# ASCII_10_FPGA_misc.net
KiCad netlist of a schematic drawn in Altium Designer
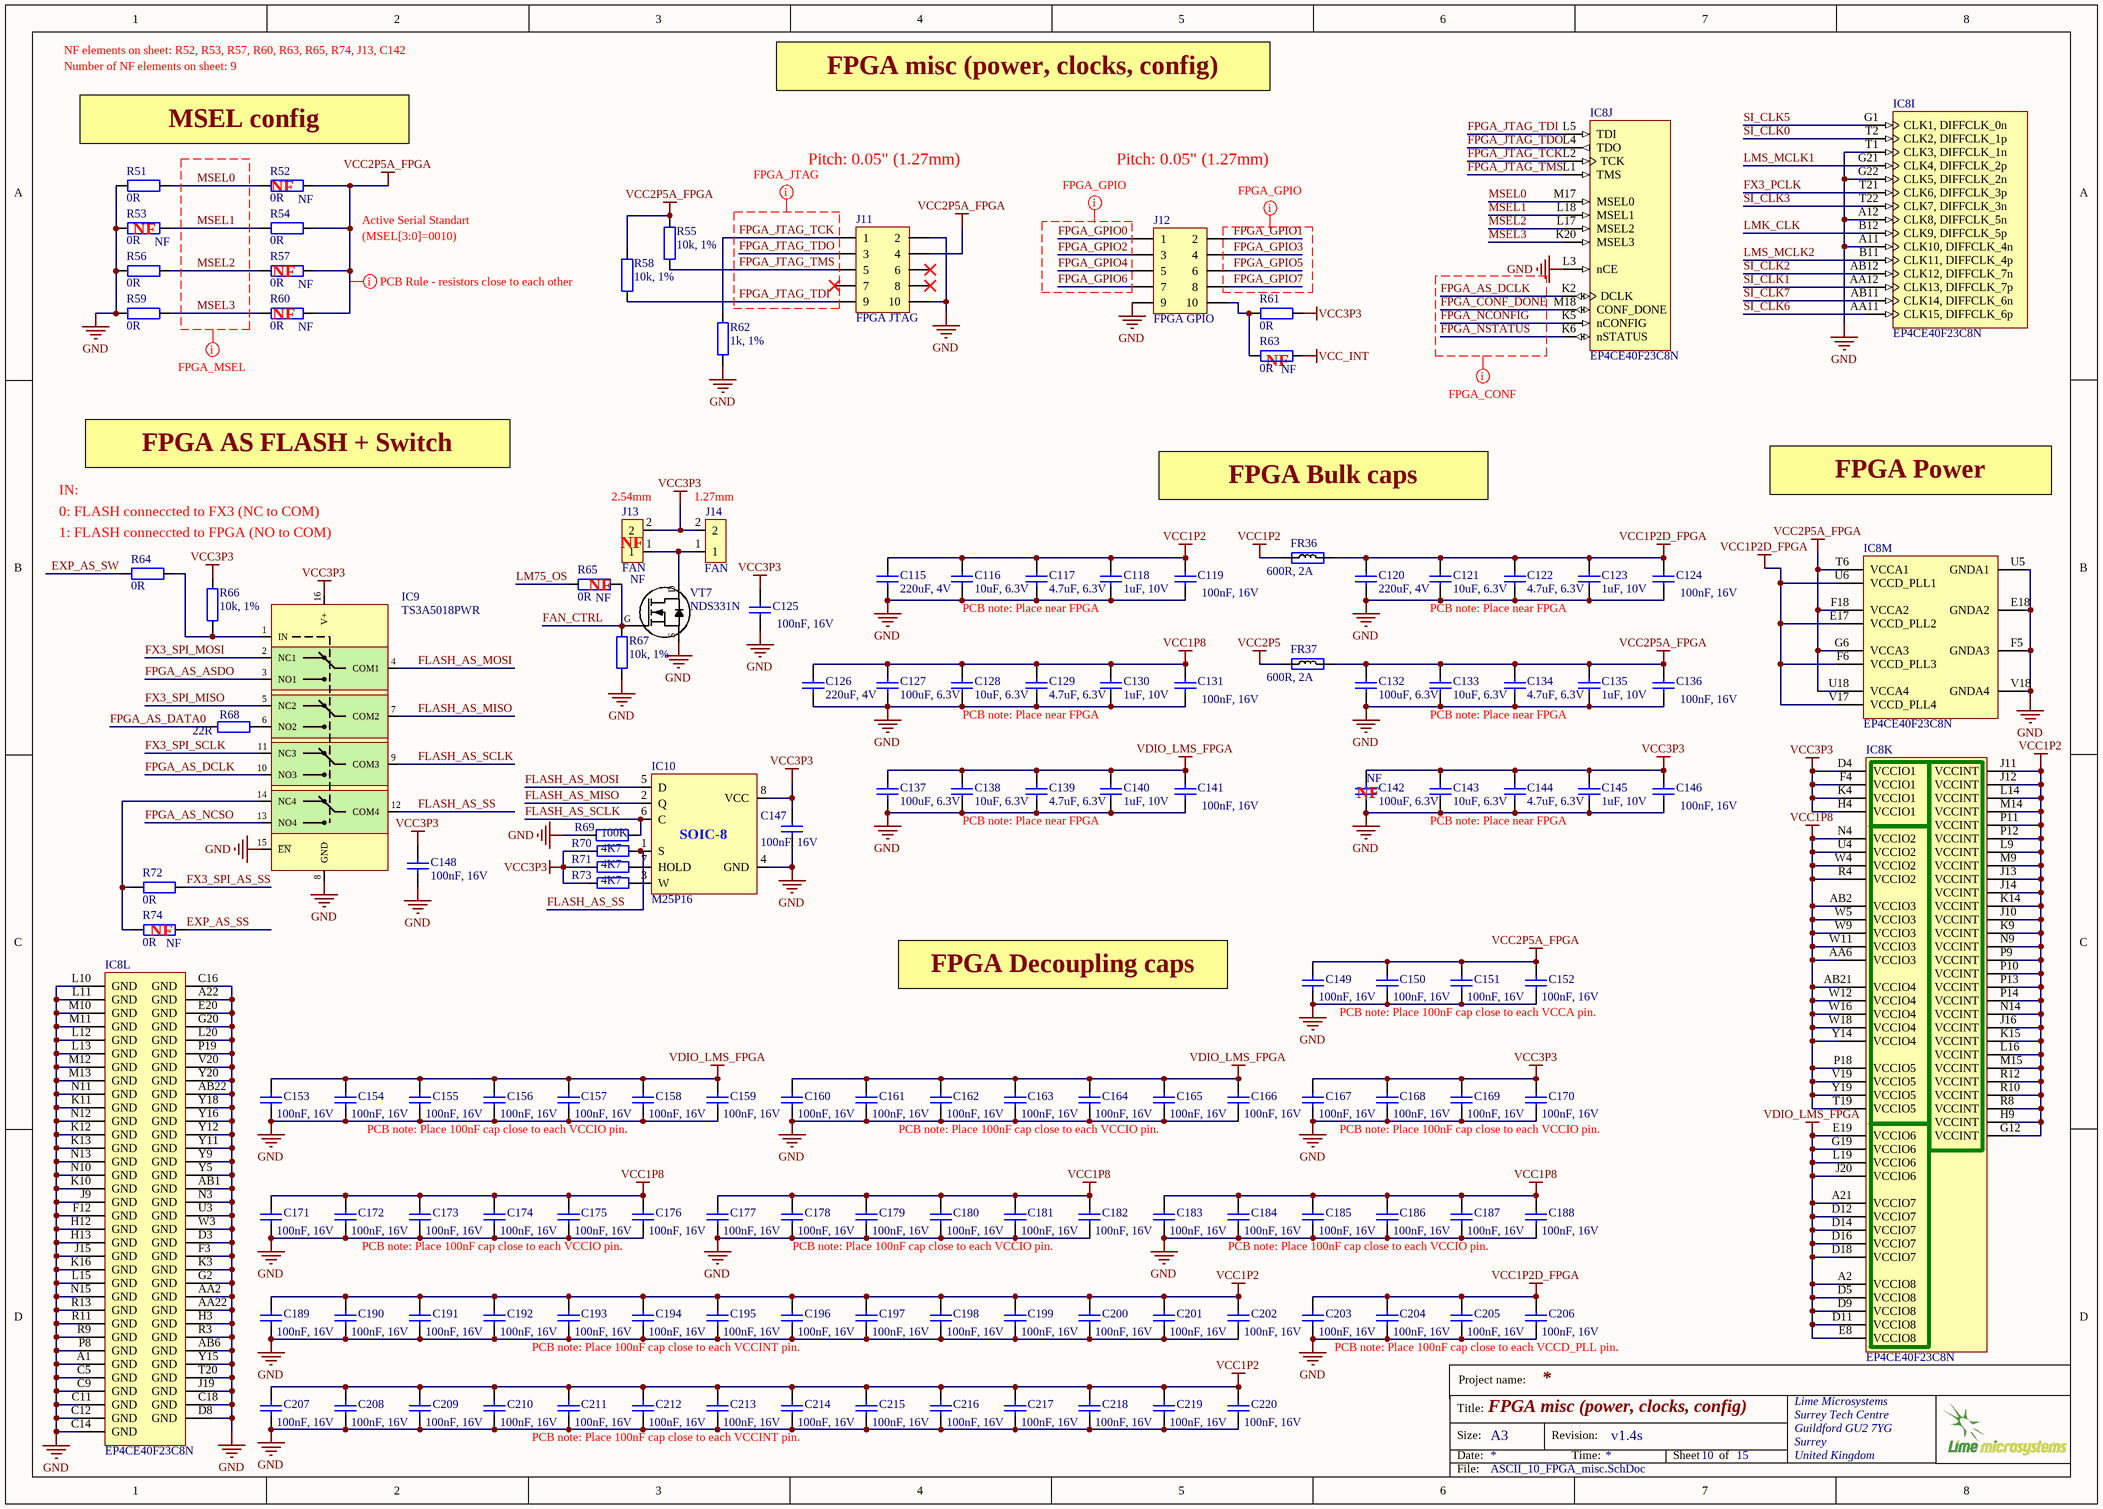
[diagram p0: ASCII_10_FPGA_misc.SchDoc]

(export (version "E")
  (design (tool "Eeschema 10.0.6"))
  (components
    (comp (ref "C115")
      (value "220uF, 4V")
      (footprint "CAP1206")
      (fields
        (field (name "MANUFACTURER PART NUMBER") "GRM31CR60G227ME11L")
        (field (name "MANUFACTURER") "Murata Electronics North America")
        (field (name "TOLERANCE") "±20%")
      )
      (libsource (lib "LimeFPGAboard_schLib") (part "Cap_1206"))
    )
    (comp (ref "C116")
      (value "10uF, 6.3V")
      (footprint "CAP0603")
      (fields (field (name "TOLERANCE") "±20%") (field (name "MANUFACTURER") "Yageo"))
      (libsource (lib "LimeFPGAboard_schLib") (part "Cap_0603"))
    )
    (comp (ref "C117")
      (value "4.7uF, 6.3V")
      (footprint "CAP0402")
      (fields
        (field (name "MANUFACTURER") "Murata Electronics North America")
        (field (name "TOLERANCE") "±20%")
        (field (name "MANUFACTURER PART NUMBER") "GRM155R60J475ME87D")
      )
      (libsource (lib "LimeMicroAltiumLib_schLib") (part "Cap_0402"))
    )
    (comp (ref "C118")
      (value "1uF, 10V")
      (footprint "CAP0402")
      (fields (field (name "MANUFACTURER") "TDK"))
      (libsource (lib "LimeMicroAltiumLib_schLib") (part "Cap_0402"))
    )
    (comp (ref "C119")
      (value "100nF, 16V")
      (footprint "CAP0402")
      (fields
        (field (name "TOLERANCE") "10 %")
        (field (name "MANUFACTURER") "Murata Electronics")
        (field (name "MANUFACTURER PART NUMBER") "GRM155R71C104KA88D")
      )
      (libsource (lib "LimeFPGAboard_schLib") (part "Cap_0603"))
    )
    (comp (ref "C120")
      (value "220uF, 4V")
      (footprint "CAP1206")
      (fields
        (field (name "MANUFACTURER PART NUMBER") "GRM31CR60G227ME11L")
        (field (name "MANUFACTURER") "Murata Electronics North America")
        (field (name "TOLERANCE") "±20%")
      )
      (libsource (lib "LimeFPGAboard_schLib") (part "Cap_1206"))
    )
    (comp (ref "C121")
      (value "10uF, 6.3V")
      (footprint "CAP0603")
      (fields (field (name "TOLERANCE") "±20%") (field (name "MANUFACTURER") "Yageo"))
      (libsource (lib "LimeFPGAboard_schLib") (part "Cap_0603"))
    )
    (comp (ref "C122")
      (value "4.7uF, 6.3V")
      (footprint "CAP0402")
      (fields
        (field (name "MANUFACTURER") "Murata Electronics North America")
        (field (name "TOLERANCE") "±20%")
        (field (name "MANUFACTURER PART NUMBER") "GRM155R60J475ME87D")
      )
      (libsource (lib "LimeMicroAltiumLib_schLib") (part "Cap_0402"))
    )
    (comp (ref "C123")
      (value "1uF, 10V")
      (footprint "CAP0402")
      (fields (field (name "MANUFACTURER") "TDK"))
      (libsource (lib "LimeMicroAltiumLib_schLib") (part "Cap_0402"))
    )
    (comp (ref "C124")
      (value "100nF, 16V")
      (footprint "CAP0402")
      (fields
        (field (name "TOLERANCE") "10 %")
        (field (name "MANUFACTURER") "Murata Electronics")
        (field (name "MANUFACTURER PART NUMBER") "GRM155R71C104KA88D")
      )
      (libsource (lib "LimeFPGAboard_schLib") (part "Cap_0603"))
    )
    (comp (ref "C125")
      (value "100nF, 16V")
      (footprint "CAP0402")
      (fields
        (field (name "TOLERANCE") "10 %")
        (field (name "MANUFACTURER") "Murata Electronics")
        (field (name "MANUFACTURER PART NUMBER") "GRM155R71C104KA88D")
      )
      (libsource (lib "LimeFPGAboard_schLib") (part "Cap_0603"))
    )
    (comp (ref "C126")
      (value "220uF, 4V")
      (footprint "CAP1206")
      (fields
        (field (name "MANUFACTURER PART NUMBER") "GRM31CR60G227ME11L")
        (field (name "MANUFACTURER") "Murata Electronics North America")
        (field (name "TOLERANCE") "±20%")
      )
      (libsource (lib "LimeFPGAboard_schLib") (part "Cap_1206"))
    )
    (comp (ref "C127")
      (value "100uF, 6.3V")
      (footprint "CAP1206")
      (fields (field (name "MANUFACTURER") "Murata Electronics North America"))
      (libsource (lib "LimeFPGAboard_schLib") (part "Cap_1206"))
    )
    (comp (ref "C128")
      (value "10uF, 6.3V")
      (footprint "CAP0603")
      (fields (field (name "TOLERANCE") "±20%") (field (name "MANUFACTURER") "Yageo"))
      (libsource (lib "LimeFPGAboard_schLib") (part "Cap_0603"))
    )
    (comp (ref "C129")
      (value "4.7uF, 6.3V")
      (footprint "CAP0402")
      (fields
        (field (name "MANUFACTURER") "Murata Electronics North America")
        (field (name "TOLERANCE") "±20%")
        (field (name "MANUFACTURER PART NUMBER") "GRM155R60J475ME87D")
      )
      (libsource (lib "LimeMicroAltiumLib_schLib") (part "Cap_0402"))
    )
    (comp (ref "C130")
      (value "1uF, 10V")
      (footprint "CAP0402")
      (fields (field (name "MANUFACTURER") "TDK"))
      (libsource (lib "LimeMicroAltiumLib_schLib") (part "Cap_0402"))
    )
    (comp (ref "C131")
      (value "100nF, 16V")
      (footprint "CAP0402")
      (fields
        (field (name "TOLERANCE") "10 %")
        (field (name "MANUFACTURER") "Murata Electronics")
        (field (name "MANUFACTURER PART NUMBER") "GRM155R71C104KA88D")
      )
      (libsource (lib "LimeFPGAboard_schLib") (part "Cap_0603"))
    )
    (comp (ref "C132")
      (value "100uF, 6.3V")
      (footprint "CAP1206")
      (fields (field (name "MANUFACTURER") "Murata Electronics North America"))
      (libsource (lib "LimeFPGAboard_schLib") (part "Cap_1206"))
    )
    (comp (ref "C133")
      (value "10uF, 6.3V")
      (footprint "CAP0603")
      (fields (field (name "TOLERANCE") "±20%") (field (name "MANUFACTURER") "Yageo"))
      (libsource (lib "LimeFPGAboard_schLib") (part "Cap_0603"))
    )
    (comp (ref "C134")
      (value "4.7uF, 6.3V")
      (footprint "CAP0402")
      (fields
        (field (name "MANUFACTURER") "Murata Electronics North America")
        (field (name "TOLERANCE") "±20%")
        (field (name "MANUFACTURER PART NUMBER") "GRM155R60J475ME87D")
      )
      (libsource (lib "LimeMicroAltiumLib_schLib") (part "Cap_0402"))
    )
    (comp (ref "C135")
      (value "1uF, 10V")
      (footprint "CAP0402")
      (fields (field (name "MANUFACTURER") "TDK"))
      (libsource (lib "LimeMicroAltiumLib_schLib") (part "Cap_0402"))
    )
    (comp (ref "C136")
      (value "100nF, 16V")
      (footprint "CAP0402")
      (fields
        (field (name "TOLERANCE") "10 %")
        (field (name "MANUFACTURER") "Murata Electronics")
        (field (name "MANUFACTURER PART NUMBER") "GRM155R71C104KA88D")
      )
      (libsource (lib "LimeFPGAboard_schLib") (part "Cap_0603"))
    )
    (comp (ref "C137")
      (value "100uF, 6.3V")
      (footprint "CAP1206")
      (fields (field (name "MANUFACTURER") "Murata Electronics North America"))
      (libsource (lib "LimeFPGAboard_schLib") (part "Cap_1206"))
    )
    (comp (ref "C138")
      (value "10uF, 6.3V")
      (footprint "CAP0603")
      (fields (field (name "TOLERANCE") "±20%") (field (name "MANUFACTURER") "Yageo"))
      (libsource (lib "LimeFPGAboard_schLib") (part "Cap_0603"))
    )
    (comp (ref "C139")
      (value "4.7uF, 6.3V")
      (footprint "CAP0402")
      (fields
        (field (name "MANUFACTURER") "Murata Electronics North America")
        (field (name "TOLERANCE") "±20%")
        (field (name "MANUFACTURER PART NUMBER") "GRM155R60J475ME87D")
      )
      (libsource (lib "LimeMicroAltiumLib_schLib") (part "Cap_0402"))
    )
    (comp (ref "C140")
      (value "1uF, 10V")
      (footprint "CAP0402")
      (fields (field (name "MANUFACTURER") "TDK"))
      (libsource (lib "LimeMicroAltiumLib_schLib") (part "Cap_0402"))
    )
    (comp (ref "C141")
      (value "100nF, 16V")
      (footprint "CAP0402")
      (fields
        (field (name "TOLERANCE") "10 %")
        (field (name "MANUFACTURER") "Murata Electronics")
        (field (name "MANUFACTURER PART NUMBER") "GRM155R71C104KA88D")
      )
      (libsource (lib "LimeFPGAboard_schLib") (part "Cap_0603"))
    )
    (comp (ref "C142")
      (value "100uF, 6.3V")
      (footprint "CAP1206")
      (fields
        (field (name "MANUFACTURER") "Murata Electronics North America")
        (field (name "ASSEMBLY INFO") "NF")
      )
      (libsource (lib "LimeFPGAboard_schLib") (part "Cap_1206"))
    )
    (comp (ref "C143")
      (value "10uF, 6.3V")
      (footprint "CAP0603")
      (fields (field (name "TOLERANCE") "±20%") (field (name "MANUFACTURER") "Yageo"))
      (libsource (lib "LimeFPGAboard_schLib") (part "Cap_0603"))
    )
    (comp (ref "C144")
      (value "4.7uF, 6.3V")
      (footprint "CAP0402")
      (fields
        (field (name "MANUFACTURER") "Murata Electronics North America")
        (field (name "TOLERANCE") "±20%")
        (field (name "MANUFACTURER PART NUMBER") "GRM155R60J475ME87D")
      )
      (libsource (lib "LimeMicroAltiumLib_schLib") (part "Cap_0402"))
    )
    (comp (ref "C145")
      (value "1uF, 10V")
      (footprint "CAP0402")
      (fields (field (name "MANUFACTURER") "TDK"))
      (libsource (lib "LimeMicroAltiumLib_schLib") (part "Cap_0402"))
    )
    (comp (ref "C146")
      (value "100nF, 16V")
      (footprint "CAP0402")
      (fields
        (field (name "TOLERANCE") "10 %")
        (field (name "MANUFACTURER") "Murata Electronics")
        (field (name "MANUFACTURER PART NUMBER") "GRM155R71C104KA88D")
      )
      (libsource (lib "LimeFPGAboard_schLib") (part "Cap_0603"))
    )
    (comp (ref "C147")
      (value "100nF, 16V")
      (footprint "CAP0402")
      (fields
        (field (name "TOLERANCE") "10 %")
        (field (name "MANUFACTURER") "Murata Electronics")
        (field (name "MANUFACTURER PART NUMBER") "GRM155R71C104KA88D")
      )
      (libsource (lib "LimeFPGAboard_schLib") (part "Cap_0603"))
    )
    (comp (ref "C148")
      (value "100nF, 16V")
      (footprint "CAP0402")
      (fields
        (field (name "TOLERANCE") "10 %")
        (field (name "MANUFACTURER") "Murata Electronics")
        (field (name "MANUFACTURER PART NUMBER") "GRM155R71C104KA88D")
      )
      (libsource (lib "LimeFPGAboard_schLib") (part "Cap_0603"))
    )
    (comp (ref "C149")
      (value "100nF, 16V")
      (footprint "CAP0402")
      (fields
        (field (name "TOLERANCE") "10 %")
        (field (name "MANUFACTURER") "Murata Electronics")
        (field (name "MANUFACTURER PART NUMBER") "GRM155R71C104KA88D")
      )
      (libsource (lib "LimeFPGAboard_schLib") (part "Cap_0603"))
    )
    (comp (ref "C150")
      (value "100nF, 16V")
      (footprint "CAP0402")
      (fields
        (field (name "TOLERANCE") "10 %")
        (field (name "MANUFACTURER") "Murata Electronics")
        (field (name "MANUFACTURER PART NUMBER") "GRM155R71C104KA88D")
      )
      (libsource (lib "LimeFPGAboard_schLib") (part "Cap_0603"))
    )
    (comp (ref "C151")
      (value "100nF, 16V")
      (footprint "CAP0402")
      (fields
        (field (name "TOLERANCE") "10 %")
        (field (name "MANUFACTURER") "Murata Electronics")
        (field (name "MANUFACTURER PART NUMBER") "GRM155R71C104KA88D")
      )
      (libsource (lib "LimeFPGAboard_schLib") (part "Cap_0603"))
    )
    (comp (ref "C152")
      (value "100nF, 16V")
      (footprint "CAP0402")
      (fields
        (field (name "TOLERANCE") "10 %")
        (field (name "MANUFACTURER") "Murata Electronics")
        (field (name "MANUFACTURER PART NUMBER") "GRM155R71C104KA88D")
      )
      (libsource (lib "LimeFPGAboard_schLib") (part "Cap_0603"))
    )
    (comp (ref "C153")
      (value "100nF, 16V")
      (footprint "CAP0402")
      (fields
        (field (name "TOLERANCE") "10 %")
        (field (name "MANUFACTURER") "Murata Electronics")
        (field (name "MANUFACTURER PART NUMBER") "GRM155R71C104KA88D")
      )
      (libsource (lib "LimeFPGAboard_schLib") (part "Cap_0603"))
    )
    (comp (ref "C154")
      (value "100nF, 16V")
      (footprint "CAP0402")
      (fields
        (field (name "TOLERANCE") "10 %")
        (field (name "MANUFACTURER") "Murata Electronics")
        (field (name "MANUFACTURER PART NUMBER") "GRM155R71C104KA88D")
      )
      (libsource (lib "LimeFPGAboard_schLib") (part "Cap_0603"))
    )
    (comp (ref "C155")
      (value "100nF, 16V")
      (footprint "CAP0402")
      (fields
        (field (name "TOLERANCE") "10 %")
        (field (name "MANUFACTURER") "Murata Electronics")
        (field (name "MANUFACTURER PART NUMBER") "GRM155R71C104KA88D")
      )
      (libsource (lib "LimeFPGAboard_schLib") (part "Cap_0603"))
    )
    (comp (ref "C156")
      (value "100nF, 16V")
      (footprint "CAP0402")
      (fields
        (field (name "TOLERANCE") "10 %")
        (field (name "MANUFACTURER") "Murata Electronics")
        (field (name "MANUFACTURER PART NUMBER") "GRM155R71C104KA88D")
      )
      (libsource (lib "LimeFPGAboard_schLib") (part "Cap_0603"))
    )
    (comp (ref "C157")
      (value "100nF, 16V")
      (footprint "CAP0402")
      (fields
        (field (name "TOLERANCE") "10 %")
        (field (name "MANUFACTURER") "Murata Electronics")
        (field (name "MANUFACTURER PART NUMBER") "GRM155R71C104KA88D")
      )
      (libsource (lib "LimeFPGAboard_schLib") (part "Cap_0603"))
    )
    (comp (ref "C158")
      (value "100nF, 16V")
      (footprint "CAP0402")
      (fields
        (field (name "TOLERANCE") "10 %")
        (field (name "MANUFACTURER") "Murata Electronics")
        (field (name "MANUFACTURER PART NUMBER") "GRM155R71C104KA88D")
      )
      (libsource (lib "LimeFPGAboard_schLib") (part "Cap_0603"))
    )
    (comp (ref "C159")
      (value "100nF, 16V")
      (footprint "CAP0402")
      (fields
        (field (name "TOLERANCE") "10 %")
        (field (name "MANUFACTURER") "Murata Electronics")
        (field (name "MANUFACTURER PART NUMBER") "GRM155R71C104KA88D")
      )
      (libsource (lib "LimeFPGAboard_schLib") (part "Cap_0603"))
    )
    (comp (ref "C160")
      (value "100nF, 16V")
      (footprint "CAP0402")
      (fields
        (field (name "TOLERANCE") "10 %")
        (field (name "MANUFACTURER") "Murata Electronics")
        (field (name "MANUFACTURER PART NUMBER") "GRM155R71C104KA88D")
      )
      (libsource (lib "LimeFPGAboard_schLib") (part "Cap_0603"))
    )
    (comp (ref "C161")
      (value "100nF, 16V")
      (footprint "CAP0402")
      (fields
        (field (name "TOLERANCE") "10 %")
        (field (name "MANUFACTURER") "Murata Electronics")
        (field (name "MANUFACTURER PART NUMBER") "GRM155R71C104KA88D")
      )
      (libsource (lib "LimeFPGAboard_schLib") (part "Cap_0603"))
    )
    (comp (ref "C162")
      (value "100nF, 16V")
      (footprint "CAP0402")
      (fields
        (field (name "TOLERANCE") "10 %")
        (field (name "MANUFACTURER") "Murata Electronics")
        (field (name "MANUFACTURER PART NUMBER") "GRM155R71C104KA88D")
      )
      (libsource (lib "LimeFPGAboard_schLib") (part "Cap_0603"))
    )
    (comp (ref "C163")
      (value "100nF, 16V")
      (footprint "CAP0402")
      (fields
        (field (name "TOLERANCE") "10 %")
        (field (name "MANUFACTURER") "Murata Electronics")
        (field (name "MANUFACTURER PART NUMBER") "GRM155R71C104KA88D")
      )
      (libsource (lib "LimeFPGAboard_schLib") (part "Cap_0603"))
    )
    (comp (ref "C164")
      (value "100nF, 16V")
      (footprint "CAP0402")
      (fields
        (field (name "TOLERANCE") "10 %")
        (field (name "MANUFACTURER") "Murata Electronics")
        (field (name "MANUFACTURER PART NUMBER") "GRM155R71C104KA88D")
      )
      (libsource (lib "LimeFPGAboard_schLib") (part "Cap_0603"))
    )
    (comp (ref "C165")
      (value "100nF, 16V")
      (footprint "CAP0402")
      (fields
        (field (name "TOLERANCE") "10 %")
        (field (name "MANUFACTURER") "Murata Electronics")
        (field (name "MANUFACTURER PART NUMBER") "GRM155R71C104KA88D")
      )
      (libsource (lib "LimeFPGAboard_schLib") (part "Cap_0603"))
    )
    (comp (ref "C166")
      (value "100nF, 16V")
      (footprint "CAP0402")
      (fields
        (field (name "TOLERANCE") "10 %")
        (field (name "MANUFACTURER") "Murata Electronics")
        (field (name "MANUFACTURER PART NUMBER") "GRM155R71C104KA88D")
      )
      (libsource (lib "LimeFPGAboard_schLib") (part "Cap_0603"))
    )
    (comp (ref "C167")
      (value "100nF, 16V")
      (footprint "CAP0402")
      (fields
        (field (name "TOLERANCE") "10 %")
        (field (name "MANUFACTURER") "Murata Electronics")
        (field (name "MANUFACTURER PART NUMBER") "GRM155R71C104KA88D")
      )
      (libsource (lib "LimeFPGAboard_schLib") (part "Cap_0603"))
    )
    (comp (ref "C168")
      (value "100nF, 16V")
      (footprint "CAP0402")
      (fields
        (field (name "TOLERANCE") "10 %")
        (field (name "MANUFACTURER") "Murata Electronics")
        (field (name "MANUFACTURER PART NUMBER") "GRM155R71C104KA88D")
      )
      (libsource (lib "LimeFPGAboard_schLib") (part "Cap_0603"))
    )
    (comp (ref "C169")
      (value "100nF, 16V")
      (footprint "CAP0402")
      (fields
        (field (name "TOLERANCE") "10 %")
        (field (name "MANUFACTURER") "Murata Electronics")
        (field (name "MANUFACTURER PART NUMBER") "GRM155R71C104KA88D")
      )
      (libsource (lib "LimeFPGAboard_schLib") (part "Cap_0603"))
    )
    (comp (ref "C170")
      (value "100nF, 16V")
      (footprint "CAP0402")
      (fields
        (field (name "TOLERANCE") "10 %")
        (field (name "MANUFACTURER") "Murata Electronics")
        (field (name "MANUFACTURER PART NUMBER") "GRM155R71C104KA88D")
      )
      (libsource (lib "LimeFPGAboard_schLib") (part "Cap_0603"))
    )
    (comp (ref "C171")
      (value "100nF, 16V")
      (footprint "CAP0402")
      (fields
        (field (name "TOLERANCE") "10 %")
        (field (name "MANUFACTURER") "Murata Electronics")
        (field (name "MANUFACTURER PART NUMBER") "GRM155R71C104KA88D")
      )
      (libsource (lib "LimeFPGAboard_schLib") (part "Cap_0603"))
    )
    (comp (ref "C172")
      (value "100nF, 16V")
      (footprint "CAP0402")
      (fields
        (field (name "TOLERANCE") "10 %")
        (field (name "MANUFACTURER") "Murata Electronics")
        (field (name "MANUFACTURER PART NUMBER") "GRM155R71C104KA88D")
      )
      (libsource (lib "LimeFPGAboard_schLib") (part "Cap_0603"))
    )
    (comp (ref "C173")
      (value "100nF, 16V")
      (footprint "CAP0402")
      (fields
        (field (name "TOLERANCE") "10 %")
        (field (name "MANUFACTURER") "Murata Electronics")
        (field (name "MANUFACTURER PART NUMBER") "GRM155R71C104KA88D")
      )
      (libsource (lib "LimeFPGAboard_schLib") (part "Cap_0603"))
    )
    (comp (ref "C174")
      (value "100nF, 16V")
      (footprint "CAP0402")
      (fields
        (field (name "TOLERANCE") "10 %")
        (field (name "MANUFACTURER") "Murata Electronics")
        (field (name "MANUFACTURER PART NUMBER") "GRM155R71C104KA88D")
      )
      (libsource (lib "LimeFPGAboard_schLib") (part "Cap_0603"))
    )
    (comp (ref "C175")
      (value "100nF, 16V")
      (footprint "CAP0402")
      (fields
        (field (name "TOLERANCE") "10 %")
        (field (name "MANUFACTURER") "Murata Electronics")
        (field (name "MANUFACTURER PART NUMBER") "GRM155R71C104KA88D")
      )
      (libsource (lib "LimeFPGAboard_schLib") (part "Cap_0603"))
    )
    (comp (ref "C176")
      (value "100nF, 16V")
      (footprint "CAP0402")
      (fields
        (field (name "TOLERANCE") "10 %")
        (field (name "MANUFACTURER") "Murata Electronics")
        (field (name "MANUFACTURER PART NUMBER") "GRM155R71C104KA88D")
      )
      (libsource (lib "LimeFPGAboard_schLib") (part "Cap_0603"))
    )
    (comp (ref "C177")
      (value "100nF, 16V")
      (footprint "CAP0402")
      (fields
        (field (name "TOLERANCE") "10 %")
        (field (name "MANUFACTURER") "Murata Electronics")
        (field (name "MANUFACTURER PART NUMBER") "GRM155R71C104KA88D")
      )
      (libsource (lib "LimeFPGAboard_schLib") (part "Cap_0603"))
    )
    (comp (ref "C178")
      (value "100nF, 16V")
      (footprint "CAP0402")
      (fields
        (field (name "TOLERANCE") "10 %")
        (field (name "MANUFACTURER") "Murata Electronics")
        (field (name "MANUFACTURER PART NUMBER") "GRM155R71C104KA88D")
      )
      (libsource (lib "LimeFPGAboard_schLib") (part "Cap_0603"))
    )
    (comp (ref "C179")
      (value "100nF, 16V")
      (footprint "CAP0402")
      (fields
        (field (name "TOLERANCE") "10 %")
        (field (name "MANUFACTURER") "Murata Electronics")
        (field (name "MANUFACTURER PART NUMBER") "GRM155R71C104KA88D")
      )
      (libsource (lib "LimeFPGAboard_schLib") (part "Cap_0603"))
    )
    (comp (ref "C180")
      (value "100nF, 16V")
      (footprint "CAP0402")
      (fields
        (field (name "TOLERANCE") "10 %")
        (field (name "MANUFACTURER") "Murata Electronics")
        (field (name "MANUFACTURER PART NUMBER") "GRM155R71C104KA88D")
      )
      (libsource (lib "LimeFPGAboard_schLib") (part "Cap_0603"))
    )
    (comp (ref "C181")
      (value "100nF, 16V")
      (footprint "CAP0402")
      (fields
        (field (name "TOLERANCE") "10 %")
        (field (name "MANUFACTURER") "Murata Electronics")
        (field (name "MANUFACTURER PART NUMBER") "GRM155R71C104KA88D")
      )
      (libsource (lib "LimeFPGAboard_schLib") (part "Cap_0603"))
    )
    (comp (ref "C182")
      (value "100nF, 16V")
      (footprint "CAP0402")
      (fields
        (field (name "TOLERANCE") "10 %")
        (field (name "MANUFACTURER") "Murata Electronics")
        (field (name "MANUFACTURER PART NUMBER") "GRM155R71C104KA88D")
      )
      (libsource (lib "LimeFPGAboard_schLib") (part "Cap_0603"))
    )
    (comp (ref "C183")
      (value "100nF, 16V")
      (footprint "CAP0402")
      (fields
        (field (name "TOLERANCE") "10 %")
        (field (name "MANUFACTURER") "Murata Electronics")
        (field (name "MANUFACTURER PART NUMBER") "GRM155R71C104KA88D")
      )
      (libsource (lib "LimeFPGAboard_schLib") (part "Cap_0603"))
    )
    (comp (ref "C184")
      (value "100nF, 16V")
      (footprint "CAP0402")
      (fields
        (field (name "TOLERANCE") "10 %")
        (field (name "MANUFACTURER") "Murata Electronics")
        (field (name "MANUFACTURER PART NUMBER") "GRM155R71C104KA88D")
      )
      (libsource (lib "LimeFPGAboard_schLib") (part "Cap_0603"))
    )
    (comp (ref "C185")
      (value "100nF, 16V")
      (footprint "CAP0402")
      (fields
        (field (name "TOLERANCE") "10 %")
        (field (name "MANUFACTURER") "Murata Electronics")
        (field (name "MANUFACTURER PART NUMBER") "GRM155R71C104KA88D")
      )
      (libsource (lib "LimeFPGAboard_schLib") (part "Cap_0603"))
    )
    (comp (ref "C186")
      (value "100nF, 16V")
      (footprint "CAP0402")
      (fields
        (field (name "TOLERANCE") "10 %")
        (field (name "MANUFACTURER") "Murata Electronics")
        (field (name "MANUFACTURER PART NUMBER") "GRM155R71C104KA88D")
      )
      (libsource (lib "LimeFPGAboard_schLib") (part "Cap_0603"))
    )
    (comp (ref "C187")
      (value "100nF, 16V")
      (footprint "CAP0402")
      (fields
        (field (name "TOLERANCE") "10 %")
        (field (name "MANUFACTURER") "Murata Electronics")
        (field (name "MANUFACTURER PART NUMBER") "GRM155R71C104KA88D")
      )
      (libsource (lib "LimeFPGAboard_schLib") (part "Cap_0603"))
    )
    (comp (ref "C188")
      (value "100nF, 16V")
      (footprint "CAP0402")
      (fields
        (field (name "TOLERANCE") "10 %")
        (field (name "MANUFACTURER") "Murata Electronics")
        (field (name "MANUFACTURER PART NUMBER") "GRM155R71C104KA88D")
      )
      (libsource (lib "LimeFPGAboard_schLib") (part "Cap_0603"))
    )
    (comp (ref "C189")
      (value "100nF, 16V")
      (footprint "CAP0402")
      (fields
        (field (name "TOLERANCE") "10 %")
        (field (name "MANUFACTURER") "Murata Electronics")
        (field (name "MANUFACTURER PART NUMBER") "GRM155R71C104KA88D")
      )
      (libsource (lib "LimeFPGAboard_schLib") (part "Cap_0603"))
    )
    (comp (ref "C190")
      (value "100nF, 16V")
      (footprint "CAP0402")
      (fields
        (field (name "TOLERANCE") "10 %")
        (field (name "MANUFACTURER") "Murata Electronics")
        (field (name "MANUFACTURER PART NUMBER") "GRM155R71C104KA88D")
      )
      (libsource (lib "LimeFPGAboard_schLib") (part "Cap_0603"))
    )
    (comp (ref "C191")
      (value "100nF, 16V")
      (footprint "CAP0402")
      (fields
        (field (name "TOLERANCE") "10 %")
        (field (name "MANUFACTURER") "Murata Electronics")
        (field (name "MANUFACTURER PART NUMBER") "GRM155R71C104KA88D")
      )
      (libsource (lib "LimeFPGAboard_schLib") (part "Cap_0603"))
    )
    (comp (ref "C192")
      (value "100nF, 16V")
      (footprint "CAP0402")
      (fields
        (field (name "TOLERANCE") "10 %")
        (field (name "MANUFACTURER") "Murata Electronics")
        (field (name "MANUFACTURER PART NUMBER") "GRM155R71C104KA88D")
      )
      (libsource (lib "LimeFPGAboard_schLib") (part "Cap_0603"))
    )
    (comp (ref "C193")
      (value "100nF, 16V")
      (footprint "CAP0402")
      (fields
        (field (name "TOLERANCE") "10 %")
        (field (name "MANUFACTURER") "Murata Electronics")
        (field (name "MANUFACTURER PART NUMBER") "GRM155R71C104KA88D")
      )
      (libsource (lib "LimeFPGAboard_schLib") (part "Cap_0603"))
    )
    (comp (ref "C194")
      (value "100nF, 16V")
      (footprint "CAP0402")
      (fields
        (field (name "TOLERANCE") "10 %")
        (field (name "MANUFACTURER") "Murata Electronics")
        (field (name "MANUFACTURER PART NUMBER") "GRM155R71C104KA88D")
      )
      (libsource (lib "LimeFPGAboard_schLib") (part "Cap_0603"))
    )
    (comp (ref "C195")
      (value "100nF, 16V")
      (footprint "CAP0402")
      (fields
        (field (name "TOLERANCE") "10 %")
        (field (name "MANUFACTURER") "Murata Electronics")
        (field (name "MANUFACTURER PART NUMBER") "GRM155R71C104KA88D")
      )
      (libsource (lib "LimeFPGAboard_schLib") (part "Cap_0603"))
    )
    (comp (ref "C196")
      (value "100nF, 16V")
      (footprint "CAP0402")
      (fields
        (field (name "TOLERANCE") "10 %")
        (field (name "MANUFACTURER") "Murata Electronics")
        (field (name "MANUFACTURER PART NUMBER") "GRM155R71C104KA88D")
      )
      (libsource (lib "LimeFPGAboard_schLib") (part "Cap_0603"))
    )
    (comp (ref "C197")
      (value "100nF, 16V")
      (footprint "CAP0402")
      (fields
        (field (name "TOLERANCE") "10 %")
        (field (name "MANUFACTURER") "Murata Electronics")
        (field (name "MANUFACTURER PART NUMBER") "GRM155R71C104KA88D")
      )
      (libsource (lib "LimeFPGAboard_schLib") (part "Cap_0603"))
    )
    (comp (ref "C198")
      (value "100nF, 16V")
      (footprint "CAP0402")
      (fields
        (field (name "TOLERANCE") "10 %")
        (field (name "MANUFACTURER") "Murata Electronics")
        (field (name "MANUFACTURER PART NUMBER") "GRM155R71C104KA88D")
      )
      (libsource (lib "LimeFPGAboard_schLib") (part "Cap_0603"))
    )
    (comp (ref "C199")
      (value "100nF, 16V")
      (footprint "CAP0402")
      (fields
        (field (name "TOLERANCE") "10 %")
        (field (name "MANUFACTURER") "Murata Electronics")
        (field (name "MANUFACTURER PART NUMBER") "GRM155R71C104KA88D")
      )
      (libsource (lib "LimeFPGAboard_schLib") (part "Cap_0603"))
    )
    (comp (ref "C200")
      (value "100nF, 16V")
      (footprint "CAP0402")
      (fields
        (field (name "TOLERANCE") "10 %")
        (field (name "MANUFACTURER") "Murata Electronics")
        (field (name "MANUFACTURER PART NUMBER") "GRM155R71C104KA88D")
      )
      (libsource (lib "LimeFPGAboard_schLib") (part "Cap_0603"))
    )
    (comp (ref "C201")
      (value "100nF, 16V")
      (footprint "CAP0402")
      (fields
        (field (name "TOLERANCE") "10 %")
        (field (name "MANUFACTURER") "Murata Electronics")
        (field (name "MANUFACTURER PART NUMBER") "GRM155R71C104KA88D")
      )
      (libsource (lib "LimeFPGAboard_schLib") (part "Cap_0603"))
    )
    (comp (ref "C202")
      (value "100nF, 16V")
      (footprint "CAP0402")
      (fields
        (field (name "TOLERANCE") "10 %")
        (field (name "MANUFACTURER") "Murata Electronics")
        (field (name "MANUFACTURER PART NUMBER") "GRM155R71C104KA88D")
      )
      (libsource (lib "LimeFPGAboard_schLib") (part "Cap_0603"))
    )
    (comp (ref "C203")
      (value "100nF, 16V")
      (footprint "CAP0402")
      (fields
        (field (name "TOLERANCE") "10 %")
        (field (name "MANUFACTURER") "Murata Electronics")
        (field (name "MANUFACTURER PART NUMBER") "GRM155R71C104KA88D")
      )
      (libsource (lib "LimeFPGAboard_schLib") (part "Cap_0603"))
    )
    (comp (ref "C204")
      (value "100nF, 16V")
      (footprint "CAP0402")
      (fields
        (field (name "TOLERANCE") "10 %")
        (field (name "MANUFACTURER") "Murata Electronics")
        (field (name "MANUFACTURER PART NUMBER") "GRM155R71C104KA88D")
      )
      (libsource (lib "LimeFPGAboard_schLib") (part "Cap_0603"))
    )
    (comp (ref "C205")
      (value "100nF, 16V")
      (footprint "CAP0402")
      (fields
        (field (name "TOLERANCE") "10 %")
        (field (name "MANUFACTURER") "Murata Electronics")
        (field (name "MANUFACTURER PART NUMBER") "GRM155R71C104KA88D")
      )
      (libsource (lib "LimeFPGAboard_schLib") (part "Cap_0603"))
    )
    (comp (ref "C206")
      (value "100nF, 16V")
      (footprint "CAP0402")
      (fields
        (field (name "TOLERANCE") "10 %")
        (field (name "MANUFACTURER") "Murata Electronics")
        (field (name "MANUFACTURER PART NUMBER") "GRM155R71C104KA88D")
      )
      (libsource (lib "LimeFPGAboard_schLib") (part "Cap_0603"))
    )
    (comp (ref "C207")
      (value "100nF, 16V")
      (footprint "CAP0402")
      (fields
        (field (name "TOLERANCE") "10 %")
        (field (name "MANUFACTURER") "Murata Electronics")
        (field (name "MANUFACTURER PART NUMBER") "GRM155R71C104KA88D")
      )
      (libsource (lib "LimeFPGAboard_schLib") (part "Cap_0603"))
    )
    (comp (ref "C208")
      (value "100nF, 16V")
      (footprint "CAP0402")
      (fields
        (field (name "TOLERANCE") "10 %")
        (field (name "MANUFACTURER") "Murata Electronics")
        (field (name "MANUFACTURER PART NUMBER") "GRM155R71C104KA88D")
      )
      (libsource (lib "LimeFPGAboard_schLib") (part "Cap_0603"))
    )
    (comp (ref "C209")
      (value "100nF, 16V")
      (footprint "CAP0402")
      (fields
        (field (name "TOLERANCE") "10 %")
        (field (name "MANUFACTURER") "Murata Electronics")
        (field (name "MANUFACTURER PART NUMBER") "GRM155R71C104KA88D")
      )
      (libsource (lib "LimeFPGAboard_schLib") (part "Cap_0603"))
    )
    (comp (ref "C210")
      (value "100nF, 16V")
      (footprint "CAP0402")
      (fields
        (field (name "TOLERANCE") "10 %")
        (field (name "MANUFACTURER") "Murata Electronics")
        (field (name "MANUFACTURER PART NUMBER") "GRM155R71C104KA88D")
      )
      (libsource (lib "LimeFPGAboard_schLib") (part "Cap_0603"))
    )
    (comp (ref "C211")
      (value "100nF, 16V")
      (footprint "CAP0402")
      (fields
        (field (name "TOLERANCE") "10 %")
        (field (name "MANUFACTURER") "Murata Electronics")
        (field (name "MANUFACTURER PART NUMBER") "GRM155R71C104KA88D")
      )
      (libsource (lib "LimeFPGAboard_schLib") (part "Cap_0603"))
    )
    (comp (ref "C212")
      (value "100nF, 16V")
      (footprint "CAP0402")
      (fields
        (field (name "TOLERANCE") "10 %")
        (field (name "MANUFACTURER") "Murata Electronics")
        (field (name "MANUFACTURER PART NUMBER") "GRM155R71C104KA88D")
      )
      (libsource (lib "LimeFPGAboard_schLib") (part "Cap_0603"))
    )
    (comp (ref "C213")
      (value "100nF, 16V")
      (footprint "CAP0402")
      (fields
        (field (name "TOLERANCE") "10 %")
        (field (name "MANUFACTURER") "Murata Electronics")
        (field (name "MANUFACTURER PART NUMBER") "GRM155R71C104KA88D")
      )
      (libsource (lib "LimeFPGAboard_schLib") (part "Cap_0603"))
    )
    (comp (ref "C214")
      (value "100nF, 16V")
      (footprint "CAP0402")
      (fields
        (field (name "TOLERANCE") "10 %")
        (field (name "MANUFACTURER") "Murata Electronics")
        (field (name "MANUFACTURER PART NUMBER") "GRM155R71C104KA88D")
      )
      (libsource (lib "LimeFPGAboard_schLib") (part "Cap_0603"))
    )
    (comp (ref "C215")
      (value "100nF, 16V")
      (footprint "CAP0402")
      (fields
        (field (name "TOLERANCE") "10 %")
        (field (name "MANUFACTURER") "Murata Electronics")
        (field (name "MANUFACTURER PART NUMBER") "GRM155R71C104KA88D")
      )
      (libsource (lib "LimeFPGAboard_schLib") (part "Cap_0603"))
    )
    (comp (ref "C216")
      (value "100nF, 16V")
      (footprint "CAP0402")
      (fields
        (field (name "TOLERANCE") "10 %")
        (field (name "MANUFACTURER") "Murata Electronics")
        (field (name "MANUFACTURER PART NUMBER") "GRM155R71C104KA88D")
      )
      (libsource (lib "LimeFPGAboard_schLib") (part "Cap_0603"))
    )
    (comp (ref "C217")
      (value "100nF, 16V")
      (footprint "CAP0402")
      (fields
        (field (name "TOLERANCE") "10 %")
        (field (name "MANUFACTURER") "Murata Electronics")
        (field (name "MANUFACTURER PART NUMBER") "GRM155R71C104KA88D")
      )
      (libsource (lib "LimeFPGAboard_schLib") (part "Cap_0603"))
    )
    (comp (ref "C218")
      (value "100nF, 16V")
      (footprint "CAP0402")
      (fields
        (field (name "TOLERANCE") "10 %")
        (field (name "MANUFACTURER") "Murata Electronics")
        (field (name "MANUFACTURER PART NUMBER") "GRM155R71C104KA88D")
      )
      (libsource (lib "LimeFPGAboard_schLib") (part "Cap_0603"))
    )
    (comp (ref "C219")
      (value "100nF, 16V")
      (footprint "CAP0402")
      (fields
        (field (name "TOLERANCE") "10 %")
        (field (name "MANUFACTURER") "Murata Electronics")
        (field (name "MANUFACTURER PART NUMBER") "GRM155R71C104KA88D")
      )
      (libsource (lib "LimeFPGAboard_schLib") (part "Cap_0603"))
    )
    (comp (ref "C220")
      (value "100nF, 16V")
      (footprint "CAP0402")
      (fields
        (field (name "TOLERANCE") "10 %")
        (field (name "MANUFACTURER") "Murata Electronics")
        (field (name "MANUFACTURER PART NUMBER") "GRM155R71C104KA88D")
      )
      (libsource (lib "LimeFPGAboard_schLib") (part "Cap_0603"))
    )
    (comp (ref "FR36")
      (value "600R, 2A")
      (footprint "RES0805")
      (fields (field (name "MANUFACTURER") "TDK Corporation"))
      (libsource (lib "LimeMicroAltiumLib_schLib") (part "Ferrite"))
    )
    (comp (ref "FR37")
      (value "600R, 2A")
      (footprint "RES0805")
      (fields (field (name "MANUFACTURER") "TDK Corporation"))
      (libsource (lib "LimeMicroAltiumLib_schLib") (part "Ferrite"))
    )
    (comp (ref "IC8")
      (value "EP4CE40F23C8N")
      (footprint "FBGA484_A-240")
      (description "IC FPGA 328 I/O 484FBGA")
      (fields (field (name "MANUFACTURER") "Altera"))
      (libsource (lib "LimeMicroAltiumLib_schLib") (part "EP4CE40F23C7N"))
    )
    (comp (ref "IC9")
      (value "TS3A5018PWR")
      (footprint "TS3A5018PWR")
      (fields (field (name "MANUFACTURER") "TEXAS INSTRUMENTS"))
      (libsource (lib "LimeFPGAboard_schLib") (part "TS3A5018PWR"))
    )
    (comp (ref "IC10")
      (value "M25P16")
      (footprint "M25P40-VMN6TPB_SO8N")
      (fields (field (name "MANUFACTURER") "Micron Technology Inc."))
      (libsource (lib "LimeFPGAboard_schLib") (part "M25P40"))
    )
    (comp (ref "J11")
      (value "FPGA JTAG")
      (footprint "SWD_10_pin")
      (description "Header, 5-Pin, Dual row")
      (fields (field (name "MANUFACTURER") "Harwin Inc"))
      (libsource (lib "LimeMicroAltiumLib_schLib") (part "Header 5X2_SWD"))
    )
    (comp (ref "J12")
      (value "FPGA GPIO")
      (footprint "SWD_10_pin")
      (description "Header, 5-Pin, Dual row")
      (fields (field (name "MANUFACTURER") "Harwin Inc"))
      (libsource (lib "LimeMicroAltiumLib_schLib") (part "Header 5X2_SWD"))
    )
    (comp (ref "J13")
      (value "FAN")
      (footprint "HDR_1x2")
      (fields (field (name "ASSEMBLY INFO") "NF") (field (name "MANUFACTURER") "3M"))
      (libsource (lib "LimeFPGAboard_schLib") (part "Jumper"))
    )
    (comp (ref "J14")
      (value "FAN")
      (footprint "HDR_1x2_HALF_PITCH")
      (fields (field (name "MANUFACTURER") "Sullins Connector Solutions"))
      (libsource (lib "") (part "Jumper_1"))
    )
    (comp (ref "R51")
      (value "0R")
      (footprint "RES0402")
      (fields (field (name "MANUFACTURER") "Yageo"))
      (libsource (lib "LimeFPGAboard_schLib") (part "Res_0402"))
    )
    (comp (ref "R52")
      (value "0R")
      (footprint "RES0402")
      (fields (field (name "MANUFACTURER") "Yageo") (field (name "ASSEMBLY INFO") "NF"))
      (libsource (lib "LimeFPGAboard_schLib") (part "Res_0402"))
    )
    (comp (ref "R53")
      (value "0R")
      (footprint "RES0402")
      (fields (field (name "MANUFACTURER") "Yageo") (field (name "ASSEMBLY INFO") "NF"))
      (libsource (lib "LimeFPGAboard_schLib") (part "Res_0402"))
    )
    (comp (ref "R54")
      (value "0R")
      (footprint "RES0402")
      (fields (field (name "MANUFACTURER") "Yageo"))
      (libsource (lib "LimeFPGAboard_schLib") (part "Res_0402"))
    )
    (comp (ref "R55")
      (value "10k, 1%")
      (footprint "RES0402")
      (fields (field (name "MANUFACTURER") "Yageo") (field (name "TOLERANCE") "±1%"))
      (libsource (lib "LimeMicroAltiumLib_schLib") (part "Res_0402"))
    )
    (comp (ref "R56")
      (value "0R")
      (footprint "RES0402")
      (fields (field (name "MANUFACTURER") "Yageo"))
      (libsource (lib "LimeFPGAboard_schLib") (part "Res_0402"))
    )
    (comp (ref "R57")
      (value "0R")
      (footprint "RES0402")
      (fields (field (name "MANUFACTURER") "Yageo") (field (name "ASSEMBLY INFO") "NF"))
      (libsource (lib "LimeFPGAboard_schLib") (part "Res_0402"))
    )
    (comp (ref "R58")
      (value "10k, 1%")
      (footprint "RES0402")
      (fields (field (name "MANUFACTURER") "Yageo") (field (name "TOLERANCE") "±1%"))
      (libsource (lib "LimeMicroAltiumLib_schLib") (part "Res_0402"))
    )
    (comp (ref "R59")
      (value "0R")
      (footprint "RES0402")
      (fields (field (name "MANUFACTURER") "Yageo"))
      (libsource (lib "LimeFPGAboard_schLib") (part "Res_0402"))
    )
    (comp (ref "R60")
      (value "0R")
      (footprint "RES0402")
      (fields (field (name "MANUFACTURER") "Yageo") (field (name "ASSEMBLY INFO") "NF"))
      (libsource (lib "LimeFPGAboard_schLib") (part "Res_0402"))
    )
    (comp (ref "R61")
      (value "0R")
      (footprint "RES0402")
      (fields (field (name "MANUFACTURER") "Yageo"))
      (libsource (lib "LimeFPGAboard_schLib") (part "Res_0402"))
    )
    (comp (ref "R62")
      (value "1k, 1%")
      (footprint "RES0402")
      (fields (field (name "MANUFACTURER") "Stackpole Electronics Inc") (field (name "TOLERANCE") "±1%"))
      (libsource (lib "LimeMicroAltiumLib_schLib") (part "Res_0402"))
    )
    (comp (ref "R63")
      (value "0R")
      (footprint "RES0402")
      (fields (field (name "MANUFACTURER") "Yageo") (field (name "ASSEMBLY INFO") "NF"))
      (libsource (lib "LimeFPGAboard_schLib") (part "Res_0402"))
    )
    (comp (ref "R64")
      (value "0R")
      (footprint "RES0402")
      (fields (field (name "MANUFACTURER") "Yageo"))
      (libsource (lib "LimeFPGAboard_schLib") (part "Res_0402"))
    )
    (comp (ref "R65")
      (value "0R")
      (footprint "RES0402")
      (fields (field (name "MANUFACTURER") "Yageo") (field (name "ASSEMBLY INFO") "NF"))
      (libsource (lib "LimeFPGAboard_schLib") (part "Res_0402"))
    )
    (comp (ref "R66")
      (value "10k, 1%")
      (footprint "RES0402")
      (fields (field (name "MANUFACTURER") "Yageo") (field (name "TOLERANCE") "±1%"))
      (libsource (lib "LimeMicroAltiumLib_schLib") (part "Res_0402"))
    )
    (comp (ref "R67")
      (value "10k, 1%")
      (footprint "RES0402")
      (fields (field (name "MANUFACTURER") "Yageo") (field (name "TOLERANCE") "±1%"))
      (libsource (lib "LimeMicroAltiumLib_schLib") (part "Res_0402"))
    )
    (comp (ref "R68")
      (value "22R")
      (footprint "RES0402")
      (fields (field (name "TOLERANCE") "±1%") (field (name "MANUFACTURER") "Yageo"))
      (libsource (lib "LimeFPGAboard_schLib") (part "Res_0402"))
    )
    (comp (ref "R69")
      (value "100K")
      (footprint "RES0402")
      (fields
        (field (name "TOLERANCE") "±5%")
        (field (name "MANUFACTURER") "Panasonic Electronic Components")
      )
      (libsource (lib "LimeFPGAboard_schLib") (part "Res_0402"))
    )
    (comp (ref "R70")
      (value "4K7")
      (footprint "RES0402")
      (fields (field (name "TOLERANCE") "±5%") (field (name "MANUFACTURER") "Stackpole Electronics Inc."))
      (libsource (lib "LimeFPGAboard_schLib") (part "Res_0402"))
    )
    (comp (ref "R71")
      (value "4K7")
      (footprint "RES0402")
      (fields (field (name "TOLERANCE") "±5%") (field (name "MANUFACTURER") "Stackpole Electronics Inc."))
      (libsource (lib "LimeFPGAboard_schLib") (part "Res_0402"))
    )
    (comp (ref "R72")
      (value "0R")
      (footprint "RES0402")
      (fields (field (name "MANUFACTURER") "Yageo"))
      (libsource (lib "LimeFPGAboard_schLib") (part "Res_0402"))
    )
    (comp (ref "R73")
      (value "4K7")
      (footprint "RES0402")
      (fields (field (name "TOLERANCE") "±5%") (field (name "MANUFACTURER") "Stackpole Electronics Inc."))
      (libsource (lib "LimeFPGAboard_schLib") (part "Res_0402"))
    )
    (comp (ref "R74")
      (value "0R")
      (footprint "RES0402")
      (fields (field (name "MANUFACTURER") "Yageo") (field (name "ASSEMBLY INFO") "NF"))
      (libsource (lib "LimeFPGAboard_schLib") (part "Res_0402"))
    )
    (comp (ref "VT7")
      (value "NDS331N")
      (footprint "SOT23-3")
      (fields (field (name "MANUFACTURER") "Fairchild Semiconductor"))
      (libsource (lib "LimeFPGAboard_schLib") (part "NDS331N"))
    )
  )
  (nets
    (net (code "1") (name "/EXP_AS_SS") (class "Default")
      (node (ref "R74") (pin "1") (pinfunction "1_1") (pintype "passive"))
    )
    (net (code "2") (name "/EXP_AS_SW") (class "Default")
      (node (ref "R64") (pin "2") (pinfunction "2_2") (pintype "passive"))
    )
    (net (code "3") (name "/FAN_CTRL") (class "Default")
      (node (ref "R65") (pin "2") (pinfunction "2_2") (pintype "passive"))
      (node (ref "R67") (pin "1") (pinfunction "1_1") (pintype "passive"))
      (node (ref "VT7") (pin "G") (pinfunction "G_G") (pintype "passive"))
    )
    (net (code "4") (name "/FLASH_AS_MISO") (class "Default")
      (node (ref "IC10") (pin "2") (pinfunction "Q_2") (pintype "passive"))
      (node (ref "IC9") (pin "7") (pinfunction "COM2_7") (pintype "passive"))
    )
    (net (code "5") (name "/FLASH_AS_MOSI") (class "Default")
      (node (ref "IC10") (pin "5") (pinfunction "D_5") (pintype "passive"))
      (node (ref "IC9") (pin "4") (pinfunction "COM1_4") (pintype "passive"))
    )
    (net (code "6") (name "/FLASH_AS_SCLK") (class "Default")
      (node (ref "IC10") (pin "6") (pinfunction "C_6") (pintype "passive"))
      (node (ref "IC9") (pin "9") (pinfunction "COM3_9") (pintype "passive"))
      (node (ref "R69") (pin "1") (pinfunction "1_1") (pintype "passive"))
    )
    (net (code "7") (name "/FLASH_AS_SS") (class "Default")
      (node (ref "IC10") (pin "1") (pinfunction "S_1") (pintype "passive"))
      (node (ref "IC9") (pin "12") (pinfunction "COM4_12") (pintype "passive"))
      (node (ref "R70") (pin "2") (pinfunction "2_2") (pintype "passive"))
    )
    (net (code "8") (name "/FPGA_AS_ASDO") (class "Default")
      (node (ref "IC9") (pin "3") (pinfunction "NO1_3") (pintype "passive"))
    )
    (net (code "9") (name "/FPGA_AS_DATA0") (class "Default")
      (node (ref "R68") (pin "2") (pinfunction "2_2") (pintype "passive"))
    )
    (net (code "10") (name "/FPGA_AS_DCLK") (class "Default")
      (node (ref "IC8") (pin "K2") (pinfunction "DCLK_K2") (pintype "bidirectional"))
      (node (ref "IC9") (pin "10") (pinfunction "NO3_10") (pintype "passive"))
    )
    (net (code "11") (name "/FPGA_AS_NCSO") (class "Default")
      (node (ref "IC9") (pin "13") (pinfunction "NO4_13") (pintype "passive"))
    )
    (net (code "12") (name "/FPGA_CONF_DONE") (class "Default")
      (node (ref "IC8") (pin "M18") (pinfunction "CONF_DONE_M18") (pintype "bidirectional"))
    )
    (net (code "13") (name "/FPGA_GPIO0") (class "Default")
      (node (ref "J12") (pin "1") (pinfunction "1_1") (pintype "passive"))
    )
    (net (code "14") (name "/FPGA_GPIO1") (class "Default")
      (node (ref "J12") (pin "2") (pinfunction "2_2") (pintype "passive"))
    )
    (net (code "15") (name "/FPGA_GPIO2") (class "Default")
      (node (ref "J12") (pin "3") (pinfunction "3_3") (pintype "passive"))
    )
    (net (code "16") (name "/FPGA_GPIO3") (class "Default")
      (node (ref "J12") (pin "4") (pinfunction "4_4") (pintype "passive"))
    )
    (net (code "17") (name "/FPGA_GPIO4") (class "Default")
      (node (ref "J12") (pin "5") (pinfunction "5_5") (pintype "passive"))
    )
    (net (code "18") (name "/FPGA_GPIO5") (class "Default")
      (node (ref "J12") (pin "6") (pinfunction "6_6") (pintype "passive"))
    )
    (net (code "19") (name "/FPGA_GPIO6") (class "Default")
      (node (ref "J12") (pin "7") (pinfunction "7_7") (pintype "passive"))
    )
    (net (code "20") (name "/FPGA_GPIO7") (class "Default")
      (node (ref "J12") (pin "8") (pinfunction "8_8") (pintype "passive"))
    )
    (net (code "21") (name "/FPGA_JTAG_TCK") (class "Default")
      (node (ref "IC8") (pin "L2") (pinfunction "TCK_L2") (pintype "input"))
      (node (ref "J11") (pin "1") (pinfunction "1_1") (pintype "passive"))
      (node (ref "R62") (pin "1") (pinfunction "1_1") (pintype "passive"))
    )
    (net (code "22") (name "/FPGA_JTAG_TDI") (class "Default")
      (node (ref "IC8") (pin "L5") (pinfunction "TDI_L5") (pintype "input"))
      (node (ref "J11") (pin "9") (pinfunction "9_9") (pintype "passive"))
      (node (ref "R58") (pin "1") (pinfunction "1_1") (pintype "passive"))
    )
    (net (code "23") (name "/FPGA_JTAG_TDO") (class "Default")
      (node (ref "IC8") (pin "L4") (pinfunction "TDO_L4") (pintype "output"))
      (node (ref "J11") (pin "3") (pinfunction "3_3") (pintype "passive"))
    )
    (net (code "24") (name "/FPGA_JTAG_TMS") (class "Default")
      (node (ref "IC8") (pin "L1") (pinfunction "TMS_L1") (pintype "input"))
      (node (ref "J11") (pin "5") (pinfunction "5_5") (pintype "passive"))
      (node (ref "R55") (pin "1") (pinfunction "1_1") (pintype "passive"))
    )
    (net (code "25") (name "/FPGA_NCONFIG") (class "Default")
      (node (ref "IC8") (pin "K5") (pinfunction "nCONFIG_K5") (pintype "input"))
    )
    (net (code "26") (name "/FPGA_NSTATUS") (class "Default")
      (node (ref "IC8") (pin "K6") (pinfunction "nSTATUS_K6") (pintype "bidirectional"))
    )
    (net (code "27") (name "/FX3_PCLK") (class "Default")
      (node (ref "IC8") (pin "T21") (pinfunction "CLK6,_DIFFCLK_3p_T21") (pintype "input"))
    )
    (net (code "28") (name "/FX3_SPI_AS_SS") (class "Default")
      (node (ref "R72") (pin "1") (pinfunction "1_1") (pintype "passive"))
    )
    (net (code "29") (name "/FX3_SPI_MISO") (class "Default")
      (node (ref "IC9") (pin "5") (pinfunction "NC2_5") (pintype "passive"))
    )
    (net (code "30") (name "/FX3_SPI_MOSI") (class "Default")
      (node (ref "IC9") (pin "2") (pinfunction "NC1_2") (pintype "passive"))
    )
    (net (code "31") (name "/FX3_SPI_SCLK") (class "Default")
      (node (ref "IC9") (pin "11") (pinfunction "NC3_11") (pintype "passive"))
    )
    (net (code "32") (name "/LM75_OS") (class "Default")
      (node (ref "R65") (pin "1") (pinfunction "1_1") (pintype "passive"))
    )
    (net (code "33") (name "/LMK_CLK") (class "Default")
      (node (ref "IC8") (pin "B12") (pinfunction "CLK9,_DIFFCLK_5p_B12") (pintype "input"))
    )
    (net (code "34") (name "/LMS_MCLK1") (class "Default")
      (node (ref "IC8") (pin "G21") (pinfunction "CLK4,_DIFFCLK_2p_G21") (pintype "input"))
    )
    (net (code "35") (name "/LMS_MCLK2") (class "Default")
      (node (ref "IC8") (pin "B11") (pinfunction "CLK11,_DIFFCLK_4p_B11") (pintype "input"))
    )
    (net (code "36") (name "/MSEL0") (class "Default")
      (node (ref "IC8") (pin "M17") (pinfunction "MSEL0_M17") (pintype "input"))
      (node (ref "R51") (pin "1") (pinfunction "1_1") (pintype "passive"))
      (node (ref "R52") (pin "2") (pinfunction "2_2") (pintype "passive"))
    )
    (net (code "37") (name "/MSEL1") (class "Default")
      (node (ref "IC8") (pin "L18") (pinfunction "MSEL1_L18") (pintype "input"))
      (node (ref "R53") (pin "1") (pinfunction "1_1") (pintype "passive"))
      (node (ref "R54") (pin "2") (pinfunction "2_2") (pintype "passive"))
    )
    (net (code "38") (name "/MSEL2") (class "Default")
      (node (ref "IC8") (pin "L17") (pinfunction "MSEL2_L17") (pintype "input"))
      (node (ref "R56") (pin "1") (pinfunction "1_1") (pintype "passive"))
      (node (ref "R57") (pin "2") (pinfunction "2_2") (pintype "passive"))
    )
    (net (code "39") (name "/MSEL3") (class "Default")
      (node (ref "IC8") (pin "K20") (pinfunction "MSEL3_K20") (pintype "input"))
      (node (ref "R59") (pin "1") (pinfunction "1_1") (pintype "passive"))
      (node (ref "R60") (pin "2") (pinfunction "2_2") (pintype "passive"))
    )
    (net (code "40") (name "/SI_CLK0") (class "Default")
      (node (ref "IC8") (pin "T2") (pinfunction "CLK2,_DIFFCLK_1p_T2") (pintype "input"))
    )
    (net (code "41") (name "/SI_CLK1") (class "Default")
      (node (ref "IC8") (pin "AA12") (pinfunction "CLK13,_DIFFCLK_7p_AA12") (pintype "input"))
    )
    (net (code "42") (name "/SI_CLK2") (class "Default")
      (node (ref "IC8") (pin "AB12") (pinfunction "CLK12,_DIFFCLK_7n_AB12") (pintype "input"))
    )
    (net (code "43") (name "/SI_CLK3") (class "Default")
      (node (ref "IC8") (pin "T22") (pinfunction "CLK7,_DIFFCLK_3n_T22") (pintype "input"))
    )
    (net (code "44") (name "/SI_CLK5") (class "Default")
      (node (ref "IC8") (pin "G1") (pinfunction "CLK1,_DIFFCLK_0n_G1") (pintype "input"))
    )
    (net (code "45") (name "/SI_CLK6") (class "Default")
      (node (ref "IC8") (pin "AA11") (pinfunction "CLK15,_DIFFCLK_6p_AA11") (pintype "input"))
    )
    (net (code "46") (name "/SI_CLK7") (class "Default")
      (node (ref "IC8") (pin "AB11") (pinfunction "CLK14,_DIFFCLK_6n_AB11") (pintype "input"))
    )
    (net (code "47") (name "GND") (class "Default")
      (node (ref "C115") (pin "1") (pinfunction "1_1") (pintype "passive"))
      (node (ref "C116") (pin "1") (pinfunction "1_1") (pintype "passive"))
      (node (ref "C117") (pin "1") (pinfunction "1_1") (pintype "passive"))
      (node (ref "C118") (pin "2") (pinfunction "2_2") (pintype "passive"))
      (node (ref "C119") (pin "2") (pinfunction "2_2") (pintype "passive"))
      (node (ref "C120") (pin "1") (pinfunction "1_1") (pintype "passive"))
      (node (ref "C121") (pin "1") (pinfunction "1_1") (pintype "passive"))
      (node (ref "C122") (pin "1") (pinfunction "1_1") (pintype "passive"))
      (node (ref "C123") (pin "2") (pinfunction "2_2") (pintype "passive"))
      (node (ref "C124") (pin "2") (pinfunction "2_2") (pintype "passive"))
      (node (ref "C125") (pin "2") (pinfunction "2_2") (pintype "passive"))
      (node (ref "C126") (pin "1") (pinfunction "1_1") (pintype "passive"))
      (node (ref "C127") (pin "1") (pinfunction "1_1") (pintype "passive"))
      (node (ref "C128") (pin "1") (pinfunction "1_1") (pintype "passive"))
      (node (ref "C129") (pin "1") (pinfunction "1_1") (pintype "passive"))
      (node (ref "C130") (pin "1") (pinfunction "1_1") (pintype "passive"))
      (node (ref "C131") (pin "2") (pinfunction "2_2") (pintype "passive"))
      (node (ref "C132") (pin "1") (pinfunction "1_1") (pintype "passive"))
      (node (ref "C133") (pin "1") (pinfunction "1_1") (pintype "passive"))
      (node (ref "C134") (pin "1") (pinfunction "1_1") (pintype "passive"))
      (node (ref "C135") (pin "1") (pinfunction "1_1") (pintype "passive"))
      (node (ref "C136") (pin "2") (pinfunction "2_2") (pintype "passive"))
      (node (ref "C137") (pin "1") (pinfunction "1_1") (pintype "passive"))
      (node (ref "C138") (pin "1") (pinfunction "1_1") (pintype "passive"))
      (node (ref "C139") (pin "1") (pinfunction "1_1") (pintype "passive"))
      (node (ref "C140") (pin "1") (pinfunction "1_1") (pintype "passive"))
      (node (ref "C141") (pin "2") (pinfunction "2_2") (pintype "passive"))
      (node (ref "C142") (pin "1") (pinfunction "1_1") (pintype "passive"))
      (node (ref "C143") (pin "1") (pinfunction "1_1") (pintype "passive"))
      (node (ref "C144") (pin "1") (pinfunction "1_1") (pintype "passive"))
      (node (ref "C145") (pin "1") (pinfunction "1_1") (pintype "passive"))
      (node (ref "C146") (pin "2") (pinfunction "2_2") (pintype "passive"))
      (node (ref "C147") (pin "2") (pinfunction "2_2") (pintype "passive"))
      (node (ref "C148") (pin "2") (pinfunction "2_2") (pintype "passive"))
      (node (ref "C149") (pin "2") (pinfunction "2_2") (pintype "passive"))
      (node (ref "C150") (pin "2") (pinfunction "2_2") (pintype "passive"))
      (node (ref "C151") (pin "2") (pinfunction "2_2") (pintype "passive"))
      (node (ref "C152") (pin "2") (pinfunction "2_2") (pintype "passive"))
      (node (ref "C153") (pin "2") (pinfunction "2_2") (pintype "passive"))
      (node (ref "C154") (pin "2") (pinfunction "2_2") (pintype "passive"))
      (node (ref "C155") (pin "2") (pinfunction "2_2") (pintype "passive"))
      (node (ref "C156") (pin "2") (pinfunction "2_2") (pintype "passive"))
      (node (ref "C157") (pin "2") (pinfunction "2_2") (pintype "passive"))
      (node (ref "C158") (pin "2") (pinfunction "2_2") (pintype "passive"))
      (node (ref "C159") (pin "2") (pinfunction "2_2") (pintype "passive"))
      (node (ref "C160") (pin "2") (pinfunction "2_2") (pintype "passive"))
      (node (ref "C161") (pin "2") (pinfunction "2_2") (pintype "passive"))
      (node (ref "C162") (pin "2") (pinfunction "2_2") (pintype "passive"))
      (node (ref "C163") (pin "2") (pinfunction "2_2") (pintype "passive"))
      (node (ref "C164") (pin "2") (pinfunction "2_2") (pintype "passive"))
      (node (ref "C165") (pin "2") (pinfunction "2_2") (pintype "passive"))
      (node (ref "C166") (pin "2") (pinfunction "2_2") (pintype "passive"))
      (node (ref "C167") (pin "2") (pinfunction "2_2") (pintype "passive"))
      (node (ref "C168") (pin "2") (pinfunction "2_2") (pintype "passive"))
      (node (ref "C169") (pin "2") (pinfunction "2_2") (pintype "passive"))
      (node (ref "C170") (pin "2") (pinfunction "2_2") (pintype "passive"))
      (node (ref "C171") (pin "2") (pinfunction "2_2") (pintype "passive"))
      (node (ref "C172") (pin "2") (pinfunction "2_2") (pintype "passive"))
      (node (ref "C173") (pin "2") (pinfunction "2_2") (pintype "passive"))
      (node (ref "C174") (pin "2") (pinfunction "2_2") (pintype "passive"))
      (node (ref "C175") (pin "2") (pinfunction "2_2") (pintype "passive"))
      (node (ref "C176") (pin "2") (pinfunction "2_2") (pintype "passive"))
      (node (ref "C177") (pin "2") (pinfunction "2_2") (pintype "passive"))
      (node (ref "C178") (pin "2") (pinfunction "2_2") (pintype "passive"))
      (node (ref "C179") (pin "2") (pinfunction "2_2") (pintype "passive"))
      (node (ref "C180") (pin "2") (pinfunction "2_2") (pintype "passive"))
      (node (ref "C181") (pin "2") (pinfunction "2_2") (pintype "passive"))
      (node (ref "C182") (pin "2") (pinfunction "2_2") (pintype "passive"))
      (node (ref "C183") (pin "2") (pinfunction "2_2") (pintype "passive"))
      (node (ref "C184") (pin "2") (pinfunction "2_2") (pintype "passive"))
      (node (ref "C185") (pin "2") (pinfunction "2_2") (pintype "passive"))
      (node (ref "C186") (pin "2") (pinfunction "2_2") (pintype "passive"))
      (node (ref "C187") (pin "2") (pinfunction "2_2") (pintype "passive"))
      (node (ref "C188") (pin "2") (pinfunction "2_2") (pintype "passive"))
      (node (ref "C189") (pin "2") (pinfunction "2_2") (pintype "passive"))
      (node (ref "C190") (pin "2") (pinfunction "2_2") (pintype "passive"))
      (node (ref "C191") (pin "2") (pinfunction "2_2") (pintype "passive"))
      (node (ref "C192") (pin "2") (pinfunction "2_2") (pintype "passive"))
      (node (ref "C193") (pin "2") (pinfunction "2_2") (pintype "passive"))
      (node (ref "C194") (pin "2") (pinfunction "2_2") (pintype "passive"))
      (node (ref "C195") (pin "2") (pinfunction "2_2") (pintype "passive"))
      (node (ref "C196") (pin "2") (pinfunction "2_2") (pintype "passive"))
      (node (ref "C197") (pin "2") (pinfunction "2_2") (pintype "passive"))
      (node (ref "C198") (pin "2") (pinfunction "2_2") (pintype "passive"))
      (node (ref "C199") (pin "2") (pinfunction "2_2") (pintype "passive"))
      (node (ref "C200") (pin "2") (pinfunction "2_2") (pintype "passive"))
      (node (ref "C201") (pin "2") (pinfunction "2_2") (pintype "passive"))
      (node (ref "C202") (pin "2") (pinfunction "2_2") (pintype "passive"))
      (node (ref "C203") (pin "2") (pinfunction "2_2") (pintype "passive"))
      (node (ref "C204") (pin "2") (pinfunction "2_2") (pintype "passive"))
      (node (ref "C205") (pin "2") (pinfunction "2_2") (pintype "passive"))
      (node (ref "C206") (pin "2") (pinfunction "2_2") (pintype "passive"))
      (node (ref "C207") (pin "2") (pinfunction "2_2") (pintype "passive"))
      (node (ref "C208") (pin "2") (pinfunction "2_2") (pintype "passive"))
      (node (ref "C209") (pin "2") (pinfunction "2_2") (pintype "passive"))
      (node (ref "C210") (pin "2") (pinfunction "2_2") (pintype "passive"))
      (node (ref "C211") (pin "2") (pinfunction "2_2") (pintype "passive"))
      (node (ref "C212") (pin "2") (pinfunction "2_2") (pintype "passive"))
      (node (ref "C213") (pin "2") (pinfunction "2_2") (pintype "passive"))
      (node (ref "C214") (pin "2") (pinfunction "2_2") (pintype "passive"))
      (node (ref "C215") (pin "2") (pinfunction "2_2") (pintype "passive"))
      (node (ref "C216") (pin "2") (pinfunction "2_2") (pintype "passive"))
      (node (ref "C217") (pin "2") (pinfunction "2_2") (pintype "passive"))
      (node (ref "C218") (pin "2") (pinfunction "2_2") (pintype "passive"))
      (node (ref "C219") (pin "2") (pinfunction "2_2") (pintype "passive"))
      (node (ref "C220") (pin "2") (pinfunction "2_2") (pintype "passive"))
      (node (ref "IC10") (pin "4") (pinfunction "GND_4") (pintype "passive"))
      (node (ref "IC8") (pin "A1") (pinfunction "GND_A1") (pintype "power_in"))
      (node (ref "IC8") (pin "A11") (pinfunction "CLK10,_DIFFCLK_4n_A11") (pintype "input"))
      (node (ref "IC8") (pin "A12") (pinfunction "CLK8,_DIFFCLK_5n_A12") (pintype "input"))
      (node (ref "IC8") (pin "A22") (pinfunction "GND_A22") (pintype "power_in"))
      (node (ref "IC8") (pin "AA2") (pinfunction "GND_AA2") (pintype "power_in"))
      (node (ref "IC8") (pin "AA22") (pinfunction "GND_AA22") (pintype "power_in"))
      (node (ref "IC8") (pin "AB1") (pinfunction "GND_AB1") (pintype "power_in"))
      (node (ref "IC8") (pin "AB22") (pinfunction "GND_AB22") (pintype "power_in"))
      (node (ref "IC8") (pin "AB6") (pinfunction "GND_AB6") (pintype "power_in"))
      (node (ref "IC8") (pin "C11") (pinfunction "GND_C11") (pintype "power_in"))
      (node (ref "IC8") (pin "C12") (pinfunction "GND_C12") (pintype "power_in"))
      (node (ref "IC8") (pin "C14") (pinfunction "GND_C14") (pintype "power_in"))
      (node (ref "IC8") (pin "C16") (pinfunction "GND_C16") (pintype "power_in"))
      (node (ref "IC8") (pin "C18") (pinfunction "GND_C18") (pintype "power_in"))
      (node (ref "IC8") (pin "C5") (pinfunction "GND_C5") (pintype "power_in"))
      (node (ref "IC8") (pin "C9") (pinfunction "GND_C9") (pintype "power_in"))
      (node (ref "IC8") (pin "D3") (pinfunction "GND_D3") (pintype "power_in"))
      (node (ref "IC8") (pin "D8") (pinfunction "GND_D8") (pintype "power_in"))
      (node (ref "IC8") (pin "E18") (pinfunction "GNDA2_E18") (pintype "power_in"))
      (node (ref "IC8") (pin "E20") (pinfunction "GND_E20") (pintype "power_in"))
      (node (ref "IC8") (pin "F12") (pinfunction "GND_F12") (pintype "power_in"))
      (node (ref "IC8") (pin "F3") (pinfunction "GND_F3") (pintype "power_in"))
      (node (ref "IC8") (pin "F5") (pinfunction "GNDA3_F5") (pintype "power_in"))
      (node (ref "IC8") (pin "G2") (pinfunction "GND_G2") (pintype "power_in"))
      (node (ref "IC8") (pin "G20") (pinfunction "GND_G20") (pintype "power_in"))
      (node (ref "IC8") (pin "G22") (pinfunction "CLK5,_DIFFCLK_2n_G22") (pintype "input"))
      (node (ref "IC8") (pin "H12") (pinfunction "GND_H12") (pintype "power_in"))
      (node (ref "IC8") (pin "H13") (pinfunction "GND_H13") (pintype "power_in"))
      (node (ref "IC8") (pin "H3") (pinfunction "GND_H3") (pintype "power_in"))
      (node (ref "IC8") (pin "J15") (pinfunction "GND_J15") (pintype "power_in"))
      (node (ref "IC8") (pin "J19") (pinfunction "GND_J19") (pintype "power_in"))
      (node (ref "IC8") (pin "J9") (pinfunction "GND_J9") (pintype "power_in"))
      (node (ref "IC8") (pin "K10") (pinfunction "GND_K10") (pintype "power_in"))
      (node (ref "IC8") (pin "K11") (pinfunction "GND_K11") (pintype "power_in"))
      (node (ref "IC8") (pin "K12") (pinfunction "GND_K12") (pintype "power_in"))
      (node (ref "IC8") (pin "K13") (pinfunction "GND_K13") (pintype "power_in"))
      (node (ref "IC8") (pin "K16") (pinfunction "GND_K16") (pintype "power_in"))
      (node (ref "IC8") (pin "K3") (pinfunction "GND_K3") (pintype "power_in"))
      (node (ref "IC8") (pin "L10") (pinfunction "GND_L10") (pintype "power_in"))
      (node (ref "IC8") (pin "L11") (pinfunction "GND_L11") (pintype "power_in"))
      (node (ref "IC8") (pin "L12") (pinfunction "GND_L12") (pintype "power_in"))
      (node (ref "IC8") (pin "L13") (pinfunction "GND_L13") (pintype "power_in"))
      (node (ref "IC8") (pin "L15") (pinfunction "GND_L15") (pintype "power_in"))
      (node (ref "IC8") (pin "L20") (pinfunction "GND_L20") (pintype "power_in"))
      (node (ref "IC8") (pin "L3") (pinfunction "nCE_L3") (pintype "input"))
      (node (ref "IC8") (pin "M10") (pinfunction "GND_M10") (pintype "power_in"))
      (node (ref "IC8") (pin "M11") (pinfunction "GND_M11") (pintype "power_in"))
      (node (ref "IC8") (pin "M12") (pinfunction "GND_M12") (pintype "power_in"))
      (node (ref "IC8") (pin "M13") (pinfunction "GND_M13") (pintype "power_in"))
      (node (ref "IC8") (pin "N10") (pinfunction "GND_N10") (pintype "power_in"))
      (node (ref "IC8") (pin "N11") (pinfunction "GND_N11") (pintype "power_in"))
      (node (ref "IC8") (pin "N12") (pinfunction "GND_N12") (pintype "power_in"))
      (node (ref "IC8") (pin "N13") (pinfunction "GND_N13") (pintype "power_in"))
      (node (ref "IC8") (pin "N15") (pinfunction "GND_N15") (pintype "power_in"))
      (node (ref "IC8") (pin "N3") (pinfunction "GND_N3") (pintype "power_in"))
      (node (ref "IC8") (pin "P19") (pinfunction "GND_P19") (pintype "power_in"))
      (node (ref "IC8") (pin "P8") (pinfunction "GND_P8") (pintype "power_in"))
      (node (ref "IC8") (pin "R11") (pinfunction "GND_R11") (pintype "power_in"))
      (node (ref "IC8") (pin "R13") (pinfunction "GND_R13") (pintype "power_in"))
      (node (ref "IC8") (pin "R3") (pinfunction "GND_R3") (pintype "power_in"))
      (node (ref "IC8") (pin "R9") (pinfunction "GND_R9") (pintype "power_in"))
      (node (ref "IC8") (pin "T1") (pinfunction "CLK3,_DIFFCLK_1n_T1") (pintype "input"))
      (node (ref "IC8") (pin "T20") (pinfunction "GND_T20") (pintype "power_in"))
      (node (ref "IC8") (pin "U3") (pinfunction "GND_U3") (pintype "power_in"))
      (node (ref "IC8") (pin "U5") (pinfunction "GNDA1_U5") (pintype "power_in"))
      (node (ref "IC8") (pin "V18") (pinfunction "GNDA4_V18") (pintype "power_in"))
      (node (ref "IC8") (pin "V20") (pinfunction "GND_V20") (pintype "power_in"))
      (node (ref "IC8") (pin "W3") (pinfunction "GND_W3") (pintype "power_in"))
      (node (ref "IC8") (pin "Y11") (pinfunction "GND_Y11") (pintype "power_in"))
      (node (ref "IC8") (pin "Y12") (pinfunction "GND_Y12") (pintype "power_in"))
      (node (ref "IC8") (pin "Y15") (pinfunction "GND_Y15") (pintype "power_in"))
      (node (ref "IC8") (pin "Y16") (pinfunction "GND_Y16") (pintype "power_in"))
      (node (ref "IC8") (pin "Y18") (pinfunction "GND_Y18") (pintype "power_in"))
      (node (ref "IC8") (pin "Y20") (pinfunction "GND_Y20") (pintype "power_in"))
      (node (ref "IC8") (pin "Y5") (pinfunction "GND_Y5") (pintype "power_in"))
      (node (ref "IC8") (pin "Y9") (pinfunction "GND_Y9") (pintype "power_in"))
      (node (ref "IC9") (pin "15") (pinfunction "~{EN}_15") (pintype "passive"))
      (node (ref "IC9") (pin "8") (pinfunction "GND_8") (pintype "passive"))
      (node (ref "J11") (pin "10") (pinfunction "10_10") (pintype "passive"))
      (node (ref "J11") (pin "2") (pinfunction "2_2") (pintype "passive"))
      (node (ref "J12") (pin "9") (pinfunction "9_9") (pintype "passive"))
      (node (ref "R51") (pin "2") (pinfunction "2_2") (pintype "passive"))
      (node (ref "R53") (pin "2") (pinfunction "2_2") (pintype "passive"))
      (node (ref "R56") (pin "2") (pinfunction "2_2") (pintype "passive"))
      (node (ref "R59") (pin "2") (pinfunction "2_2") (pintype "passive"))
      (node (ref "R62") (pin "2") (pinfunction "2_2") (pintype "passive"))
      (node (ref "R67") (pin "2") (pinfunction "2_2") (pintype "passive"))
      (node (ref "R69") (pin "2") (pinfunction "2_2") (pintype "passive"))
      (node (ref "VT7") (pin "S") (pinfunction "S_S") (pintype "passive"))
    )
    (net (code "48") (name "Net-(IC9-IN)") (class "Default")
      (node (ref "IC9") (pin "1") (pinfunction "IN_1") (pintype "passive"))
      (node (ref "R64") (pin "1") (pinfunction "1_1") (pintype "passive"))
      (node (ref "R66") (pin "2") (pinfunction "2_2") (pintype "passive"))
    )
    (net (code "49") (name "Net-(IC9-NC4)") (class "Default")
      (node (ref "IC9") (pin "14") (pinfunction "NC4_14") (pintype "passive"))
      (node (ref "R72") (pin "2") (pinfunction "2_2") (pintype "passive"))
      (node (ref "R74") (pin "2") (pinfunction "2_2") (pintype "passive"))
    )
    (net (code "50") (name "Net-(IC9-NO2)") (class "Default")
      (node (ref "IC9") (pin "6") (pinfunction "NO2_6") (pintype "passive"))
      (node (ref "R68") (pin "1") (pinfunction "1_1") (pintype "passive"))
    )
    (net (code "51") (name "Net-(IC10-HOLD)") (class "Default")
      (node (ref "IC10") (pin "7") (pinfunction "HOLD_7") (pintype "passive"))
      (node (ref "R71") (pin "2") (pinfunction "2_2") (pintype "passive"))
    )
    (net (code "52") (name "Net-(IC10-W)") (class "Default")
      (node (ref "IC10") (pin "3") (pinfunction "W_3") (pintype "passive"))
      (node (ref "R73") (pin "2") (pinfunction "2_2") (pintype "passive"))
    )
    (net (code "53") (name "Net-(J12-Pad10)") (class "Default")
      (node (ref "J12") (pin "10") (pinfunction "10_10") (pintype "passive"))
      (node (ref "R61") (pin "2") (pinfunction "2_2") (pintype "passive"))
      (node (ref "R63") (pin "2") (pinfunction "2_2") (pintype "passive"))
    )
    (net (code "54") (name "Net-(J13-Pad1)") (class "Default")
      (node (ref "J13") (pin "1") (pinfunction "1_1") (pintype "passive"))
      (node (ref "J14") (pin "1") (pinfunction "1_1") (pintype "passive"))
      (node (ref "VT7") (pin "D") (pinfunction "D_D") (pintype "passive"))
    )
    (net (code "55") (name "VCC1P2") (class "Default")
      (node (ref "C115") (pin "2") (pinfunction "2_2") (pintype "passive"))
      (node (ref "C116") (pin "2") (pinfunction "2_2") (pintype "passive"))
      (node (ref "C117") (pin "2") (pinfunction "2_2") (pintype "passive"))
      (node (ref "C118") (pin "1") (pinfunction "1_1") (pintype "passive"))
      (node (ref "C119") (pin "1") (pinfunction "1_1") (pintype "passive"))
      (node (ref "C189") (pin "1") (pinfunction "1_1") (pintype "passive"))
      (node (ref "C190") (pin "1") (pinfunction "1_1") (pintype "passive"))
      (node (ref "C191") (pin "1") (pinfunction "1_1") (pintype "passive"))
      (node (ref "C192") (pin "1") (pinfunction "1_1") (pintype "passive"))
      (node (ref "C193") (pin "1") (pinfunction "1_1") (pintype "passive"))
      (node (ref "C194") (pin "1") (pinfunction "1_1") (pintype "passive"))
      (node (ref "C195") (pin "1") (pinfunction "1_1") (pintype "passive"))
      (node (ref "C196") (pin "1") (pinfunction "1_1") (pintype "passive"))
      (node (ref "C197") (pin "1") (pinfunction "1_1") (pintype "passive"))
      (node (ref "C198") (pin "1") (pinfunction "1_1") (pintype "passive"))
      (node (ref "C199") (pin "1") (pinfunction "1_1") (pintype "passive"))
      (node (ref "C200") (pin "1") (pinfunction "1_1") (pintype "passive"))
      (node (ref "C201") (pin "1") (pinfunction "1_1") (pintype "passive"))
      (node (ref "C202") (pin "1") (pinfunction "1_1") (pintype "passive"))
      (node (ref "C207") (pin "1") (pinfunction "1_1") (pintype "passive"))
      (node (ref "C208") (pin "1") (pinfunction "1_1") (pintype "passive"))
      (node (ref "C209") (pin "1") (pinfunction "1_1") (pintype "passive"))
      (node (ref "C210") (pin "1") (pinfunction "1_1") (pintype "passive"))
      (node (ref "C211") (pin "1") (pinfunction "1_1") (pintype "passive"))
      (node (ref "C212") (pin "1") (pinfunction "1_1") (pintype "passive"))
      (node (ref "C213") (pin "1") (pinfunction "1_1") (pintype "passive"))
      (node (ref "C214") (pin "1") (pinfunction "1_1") (pintype "passive"))
      (node (ref "C215") (pin "1") (pinfunction "1_1") (pintype "passive"))
      (node (ref "C216") (pin "1") (pinfunction "1_1") (pintype "passive"))
      (node (ref "C217") (pin "1") (pinfunction "1_1") (pintype "passive"))
      (node (ref "C218") (pin "1") (pinfunction "1_1") (pintype "passive"))
      (node (ref "C219") (pin "1") (pinfunction "1_1") (pintype "passive"))
      (node (ref "C220") (pin "1") (pinfunction "1_1") (pintype "passive"))
      (node (ref "FR36") (pin "1") (pinfunction "1_1") (pintype "passive"))
      (node (ref "IC8") (pin "G12") (pinfunction "VCCINT_G12") (pintype "power_in"))
      (node (ref "IC8") (pin "H9") (pinfunction "VCCINT_H9") (pintype "power_in"))
      (node (ref "IC8") (pin "J10") (pinfunction "VCCINT_J10") (pintype "power_in"))
      (node (ref "IC8") (pin "J11") (pinfunction "VCCINT_J11") (pintype "power_in"))
      (node (ref "IC8") (pin "J12") (pinfunction "VCCINT_J12") (pintype "power_in"))
      (node (ref "IC8") (pin "J13") (pinfunction "VCCINT_J13") (pintype "power_in"))
      (node (ref "IC8") (pin "J14") (pinfunction "VCCINT_J14") (pintype "power_in"))
      (node (ref "IC8") (pin "J16") (pinfunction "VCCINT_J16") (pintype "power_in"))
      (node (ref "IC8") (pin "K14") (pinfunction "VCCINT_K14") (pintype "power_in"))
      (node (ref "IC8") (pin "K15") (pinfunction "VCCINT_K15") (pintype "power_in"))
      (node (ref "IC8") (pin "K9") (pinfunction "VCCINT_K9") (pintype "power_in"))
      (node (ref "IC8") (pin "L14") (pinfunction "VCCINT_L14") (pintype "power_in"))
      (node (ref "IC8") (pin "L16") (pinfunction "VCCINT_L16") (pintype "power_in"))
      (node (ref "IC8") (pin "L9") (pinfunction "VCCINT_L9") (pintype "power_in"))
      (node (ref "IC8") (pin "M14") (pinfunction "VCCINT_M14") (pintype "power_in"))
      (node (ref "IC8") (pin "M15") (pinfunction "VCCINT_M15") (pintype "power_in"))
      (node (ref "IC8") (pin "M9") (pinfunction "VCCINT_M9") (pintype "power_in"))
      (node (ref "IC8") (pin "N14") (pinfunction "VCCINT_N14") (pintype "power_in"))
      (node (ref "IC8") (pin "N9") (pinfunction "VCCINT_N9") (pintype "power_in"))
      (node (ref "IC8") (pin "P10") (pinfunction "VCCINT_P10") (pintype "power_in"))
      (node (ref "IC8") (pin "P11") (pinfunction "VCCINT_P11") (pintype "power_in"))
      (node (ref "IC8") (pin "P12") (pinfunction "VCCINT_P12") (pintype "power_in"))
      (node (ref "IC8") (pin "P13") (pinfunction "VCCINT_P13") (pintype "power_in"))
      (node (ref "IC8") (pin "P14") (pinfunction "VCCINT_P14") (pintype "power_in"))
      (node (ref "IC8") (pin "P9") (pinfunction "VCCINT_P9") (pintype "power_in"))
      (node (ref "IC8") (pin "R10") (pinfunction "VCCINT_R10") (pintype "power_in"))
      (node (ref "IC8") (pin "R12") (pinfunction "VCCINT_R12") (pintype "power_in"))
      (node (ref "IC8") (pin "R8") (pinfunction "VCCINT_R8") (pintype "power_in"))
    )
    (net (code "56") (name "VCC1P2D_FPGA") (class "Default")
      (node (ref "C120") (pin "2") (pinfunction "2_2") (pintype "passive"))
      (node (ref "C121") (pin "2") (pinfunction "2_2") (pintype "passive"))
      (node (ref "C122") (pin "2") (pinfunction "2_2") (pintype "passive"))
      (node (ref "C123") (pin "1") (pinfunction "1_1") (pintype "passive"))
      (node (ref "C124") (pin "1") (pinfunction "1_1") (pintype "passive"))
      (node (ref "C203") (pin "1") (pinfunction "1_1") (pintype "passive"))
      (node (ref "C204") (pin "1") (pinfunction "1_1") (pintype "passive"))
      (node (ref "C205") (pin "1") (pinfunction "1_1") (pintype "passive"))
      (node (ref "C206") (pin "1") (pinfunction "1_1") (pintype "passive"))
      (node (ref "FR36") (pin "2") (pinfunction "2_2") (pintype "passive"))
      (node (ref "IC8") (pin "E17") (pinfunction "VCCD_PLL2_E17") (pintype "power_in"))
      (node (ref "IC8") (pin "F6") (pinfunction "VCCD_PLL3_F6") (pintype "power_in"))
      (node (ref "IC8") (pin "U6") (pinfunction "VCCD_PLL1_U6") (pintype "power_in"))
      (node (ref "IC8") (pin "V17") (pinfunction "VCCD_PLL4_V17") (pintype "power_in"))
    )
    (net (code "57") (name "VCC1P8") (class "Default")
      (node (ref "C126") (pin "2") (pinfunction "2_2") (pintype "passive"))
      (node (ref "C127") (pin "2") (pinfunction "2_2") (pintype "passive"))
      (node (ref "C128") (pin "2") (pinfunction "2_2") (pintype "passive"))
      (node (ref "C129") (pin "2") (pinfunction "2_2") (pintype "passive"))
      (node (ref "C130") (pin "2") (pinfunction "2_2") (pintype "passive"))
      (node (ref "C131") (pin "1") (pinfunction "1_1") (pintype "passive"))
      (node (ref "C171") (pin "1") (pinfunction "1_1") (pintype "passive"))
      (node (ref "C172") (pin "1") (pinfunction "1_1") (pintype "passive"))
      (node (ref "C173") (pin "1") (pinfunction "1_1") (pintype "passive"))
      (node (ref "C174") (pin "1") (pinfunction "1_1") (pintype "passive"))
      (node (ref "C175") (pin "1") (pinfunction "1_1") (pintype "passive"))
      (node (ref "C176") (pin "1") (pinfunction "1_1") (pintype "passive"))
      (node (ref "C177") (pin "1") (pinfunction "1_1") (pintype "passive"))
      (node (ref "C178") (pin "1") (pinfunction "1_1") (pintype "passive"))
      (node (ref "C179") (pin "1") (pinfunction "1_1") (pintype "passive"))
      (node (ref "C180") (pin "1") (pinfunction "1_1") (pintype "passive"))
      (node (ref "C181") (pin "1") (pinfunction "1_1") (pintype "passive"))
      (node (ref "C182") (pin "1") (pinfunction "1_1") (pintype "passive"))
      (node (ref "C183") (pin "1") (pinfunction "1_1") (pintype "passive"))
      (node (ref "C184") (pin "1") (pinfunction "1_1") (pintype "passive"))
      (node (ref "C185") (pin "1") (pinfunction "1_1") (pintype "passive"))
      (node (ref "C186") (pin "1") (pinfunction "1_1") (pintype "passive"))
      (node (ref "C187") (pin "1") (pinfunction "1_1") (pintype "passive"))
      (node (ref "C188") (pin "1") (pinfunction "1_1") (pintype "passive"))
      (node (ref "IC8") (pin "AA6") (pinfunction "VCCIO3_AA6") (pintype "power_in"))
      (node (ref "IC8") (pin "AB2") (pinfunction "VCCIO3_AB2") (pintype "power_in"))
      (node (ref "IC8") (pin "AB21") (pinfunction "VCCIO4_AB21") (pintype "power_in"))
      (node (ref "IC8") (pin "N4") (pinfunction "VCCIO2_N4") (pintype "power_in"))
      (node (ref "IC8") (pin "P18") (pinfunction "VCCIO5_P18") (pintype "power_in"))
      (node (ref "IC8") (pin "R4") (pinfunction "VCCIO2_R4") (pintype "power_in"))
      (node (ref "IC8") (pin "T19") (pinfunction "VCCIO5_T19") (pintype "power_in"))
      (node (ref "IC8") (pin "U4") (pinfunction "VCCIO2_U4") (pintype "power_in"))
      (node (ref "IC8") (pin "V19") (pinfunction "VCCIO5_V19") (pintype "power_in"))
      (node (ref "IC8") (pin "W11") (pinfunction "VCCIO3_W11") (pintype "power_in"))
      (node (ref "IC8") (pin "W12") (pinfunction "VCCIO4_W12") (pintype "power_in"))
      (node (ref "IC8") (pin "W16") (pinfunction "VCCIO4_W16") (pintype "power_in"))
      (node (ref "IC8") (pin "W18") (pinfunction "VCCIO4_W18") (pintype "power_in"))
      (node (ref "IC8") (pin "W4") (pinfunction "VCCIO2_W4") (pintype "power_in"))
      (node (ref "IC8") (pin "W5") (pinfunction "VCCIO3_W5") (pintype "power_in"))
      (node (ref "IC8") (pin "W9") (pinfunction "VCCIO3_W9") (pintype "power_in"))
      (node (ref "IC8") (pin "Y14") (pinfunction "VCCIO4_Y14") (pintype "power_in"))
      (node (ref "IC8") (pin "Y19") (pinfunction "VCCIO5_Y19") (pintype "power_in"))
    )
    (net (code "58") (name "VCC2P5") (class "Default")
      (node (ref "FR37") (pin "1") (pinfunction "1_1") (pintype "passive"))
    )
    (net (code "59") (name "VCC2P5A_FPGA") (class "Default")
      (node (ref "C132") (pin "2") (pinfunction "2_2") (pintype "passive"))
      (node (ref "C133") (pin "2") (pinfunction "2_2") (pintype "passive"))
      (node (ref "C134") (pin "2") (pinfunction "2_2") (pintype "passive"))
      (node (ref "C135") (pin "2") (pinfunction "2_2") (pintype "passive"))
      (node (ref "C136") (pin "1") (pinfunction "1_1") (pintype "passive"))
      (node (ref "C149") (pin "1") (pinfunction "1_1") (pintype "passive"))
      (node (ref "C150") (pin "1") (pinfunction "1_1") (pintype "passive"))
      (node (ref "C151") (pin "1") (pinfunction "1_1") (pintype "passive"))
      (node (ref "C152") (pin "1") (pinfunction "1_1") (pintype "passive"))
      (node (ref "FR37") (pin "2") (pinfunction "2_2") (pintype "passive"))
      (node (ref "IC8") (pin "F18") (pinfunction "VCCA2_F18") (pintype "power_in"))
      (node (ref "IC8") (pin "G6") (pinfunction "VCCA3_G6") (pintype "power_in"))
      (node (ref "IC8") (pin "T6") (pinfunction "VCCA1_T6") (pintype "power_in"))
      (node (ref "IC8") (pin "U18") (pinfunction "VCCA4_U18") (pintype "power_in"))
      (node (ref "J11") (pin "4") (pinfunction "4_4") (pintype "passive"))
      (node (ref "R52") (pin "1") (pinfunction "1_1") (pintype "passive"))
      (node (ref "R54") (pin "1") (pinfunction "1_1") (pintype "passive"))
      (node (ref "R55") (pin "2") (pinfunction "2_2") (pintype "passive"))
      (node (ref "R57") (pin "1") (pinfunction "1_1") (pintype "passive"))
      (node (ref "R58") (pin "2") (pinfunction "2_2") (pintype "passive"))
      (node (ref "R60") (pin "1") (pinfunction "1_1") (pintype "passive"))
    )
    (net (code "60") (name "VCC3P3") (class "Default")
      (node (ref "C125") (pin "1") (pinfunction "1_1") (pintype "passive"))
      (node (ref "C142") (pin "2") (pinfunction "2_2") (pintype "passive"))
      (node (ref "C143") (pin "2") (pinfunction "2_2") (pintype "passive"))
      (node (ref "C144") (pin "2") (pinfunction "2_2") (pintype "passive"))
      (node (ref "C145") (pin "2") (pinfunction "2_2") (pintype "passive"))
      (node (ref "C146") (pin "1") (pinfunction "1_1") (pintype "passive"))
      (node (ref "C147") (pin "1") (pinfunction "1_1") (pintype "passive"))
      (node (ref "C148") (pin "1") (pinfunction "1_1") (pintype "passive"))
      (node (ref "C167") (pin "1") (pinfunction "1_1") (pintype "passive"))
      (node (ref "C168") (pin "1") (pinfunction "1_1") (pintype "passive"))
      (node (ref "C169") (pin "1") (pinfunction "1_1") (pintype "passive"))
      (node (ref "C170") (pin "1") (pinfunction "1_1") (pintype "passive"))
      (node (ref "IC10") (pin "8") (pinfunction "VCC_8") (pintype "passive"))
      (node (ref "IC8") (pin "D4") (pinfunction "VCCIO1_D4") (pintype "power_in"))
      (node (ref "IC8") (pin "F4") (pinfunction "VCCIO1_F4") (pintype "power_in"))
      (node (ref "IC8") (pin "H4") (pinfunction "VCCIO1_H4") (pintype "power_in"))
      (node (ref "IC8") (pin "K4") (pinfunction "VCCIO1_K4") (pintype "power_in"))
      (node (ref "IC9") (pin "16") (pinfunction "V+_16") (pintype "passive"))
      (node (ref "J13") (pin "2") (pinfunction "2_2") (pintype "passive"))
      (node (ref "J14") (pin "2") (pinfunction "2_2") (pintype "passive"))
      (node (ref "R61") (pin "1") (pinfunction "1_1") (pintype "passive"))
      (node (ref "R66") (pin "1") (pinfunction "1_1") (pintype "passive"))
      (node (ref "R70") (pin "1") (pinfunction "1_1") (pintype "passive"))
      (node (ref "R71") (pin "1") (pinfunction "1_1") (pintype "passive"))
      (node (ref "R73") (pin "1") (pinfunction "1_1") (pintype "passive"))
    )
    (net (code "61") (name "VCC_INT") (class "Default")
      (node (ref "R63") (pin "1") (pinfunction "1_1") (pintype "passive"))
    )
    (net (code "62") (name "VDIO_LMS_FPGA") (class "Default")
      (node (ref "C137") (pin "2") (pinfunction "2_2") (pintype "passive"))
      (node (ref "C138") (pin "2") (pinfunction "2_2") (pintype "passive"))
      (node (ref "C139") (pin "2") (pinfunction "2_2") (pintype "passive"))
      (node (ref "C140") (pin "2") (pinfunction "2_2") (pintype "passive"))
      (node (ref "C141") (pin "1") (pinfunction "1_1") (pintype "passive"))
      (node (ref "C153") (pin "1") (pinfunction "1_1") (pintype "passive"))
      (node (ref "C154") (pin "1") (pinfunction "1_1") (pintype "passive"))
      (node (ref "C155") (pin "1") (pinfunction "1_1") (pintype "passive"))
      (node (ref "C156") (pin "1") (pinfunction "1_1") (pintype "passive"))
      (node (ref "C157") (pin "1") (pinfunction "1_1") (pintype "passive"))
      (node (ref "C158") (pin "1") (pinfunction "1_1") (pintype "passive"))
      (node (ref "C159") (pin "1") (pinfunction "1_1") (pintype "passive"))
      (node (ref "C160") (pin "1") (pinfunction "1_1") (pintype "passive"))
      (node (ref "C161") (pin "1") (pinfunction "1_1") (pintype "passive"))
      (node (ref "C162") (pin "1") (pinfunction "1_1") (pintype "passive"))
      (node (ref "C163") (pin "1") (pinfunction "1_1") (pintype "passive"))
      (node (ref "C164") (pin "1") (pinfunction "1_1") (pintype "passive"))
      (node (ref "C165") (pin "1") (pinfunction "1_1") (pintype "passive"))
      (node (ref "C166") (pin "1") (pinfunction "1_1") (pintype "passive"))
      (node (ref "IC8") (pin "A2") (pinfunction "VCCIO8_A2") (pintype "power_in"))
      (node (ref "IC8") (pin "A21") (pinfunction "VCCIO7_A21") (pintype "power_in"))
      (node (ref "IC8") (pin "D11") (pinfunction "VCCIO8_D11") (pintype "power_in"))
      (node (ref "IC8") (pin "D12") (pinfunction "VCCIO7_D12") (pintype "power_in"))
      (node (ref "IC8") (pin "D14") (pinfunction "VCCIO7_D14") (pintype "power_in"))
      (node (ref "IC8") (pin "D16") (pinfunction "VCCIO7_D16") (pintype "power_in"))
      (node (ref "IC8") (pin "D18") (pinfunction "VCCIO7_D18") (pintype "power_in"))
      (node (ref "IC8") (pin "D5") (pinfunction "VCCIO8_D5") (pintype "power_in"))
      (node (ref "IC8") (pin "D9") (pinfunction "VCCIO8_D9") (pintype "power_in"))
      (node (ref "IC8") (pin "E19") (pinfunction "VCCIO6_E19") (pintype "power_in"))
      (node (ref "IC8") (pin "E8") (pinfunction "VCCIO8_E8") (pintype "power_in"))
      (node (ref "IC8") (pin "G19") (pinfunction "VCCIO6_G19") (pintype "power_in"))
      (node (ref "IC8") (pin "J20") (pinfunction "VCCIO6_J20") (pintype "power_in"))
      (node (ref "IC8") (pin "L19") (pinfunction "VCCIO6_L19") (pintype "power_in"))
    )
    (net (code "63") (name "unconnected-(J11-Pad6)") (class "Default")
      (node (ref "J11") (pin "6") (pinfunction "6_6") (pintype "passive+no_connect"))
    )
    (net (code "64") (name "unconnected-(J11-Pad7)") (class "Default")
      (node (ref "J11") (pin "7") (pinfunction "7_7") (pintype "passive+no_connect"))
    )
    (net (code "65") (name "unconnected-(J11-Pad8)") (class "Default")
      (node (ref "J11") (pin "8") (pinfunction "8_8") (pintype "passive+no_connect"))
    )
  )
)
